# tkl3.net
KiCad netlist of a schematic drawn in EAGLE
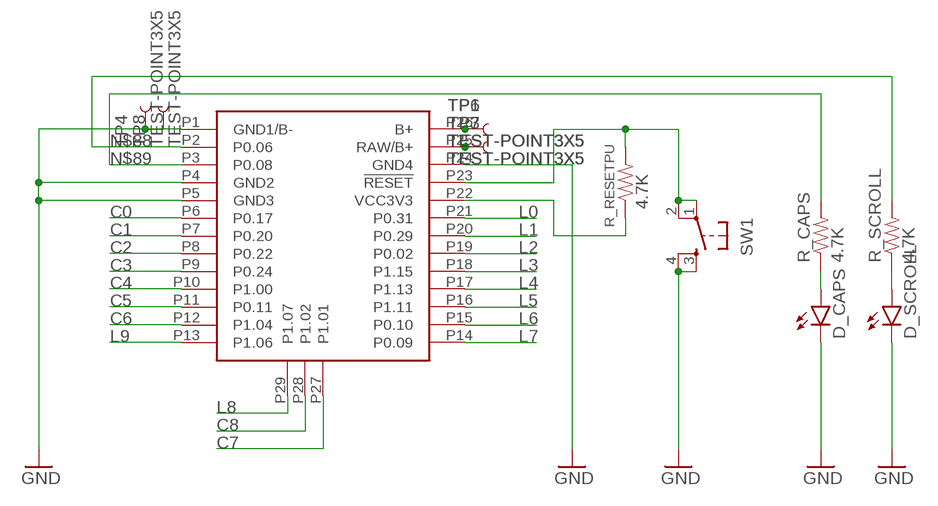
[diagram p0: schematic, sheet 1, part 1 of 2]
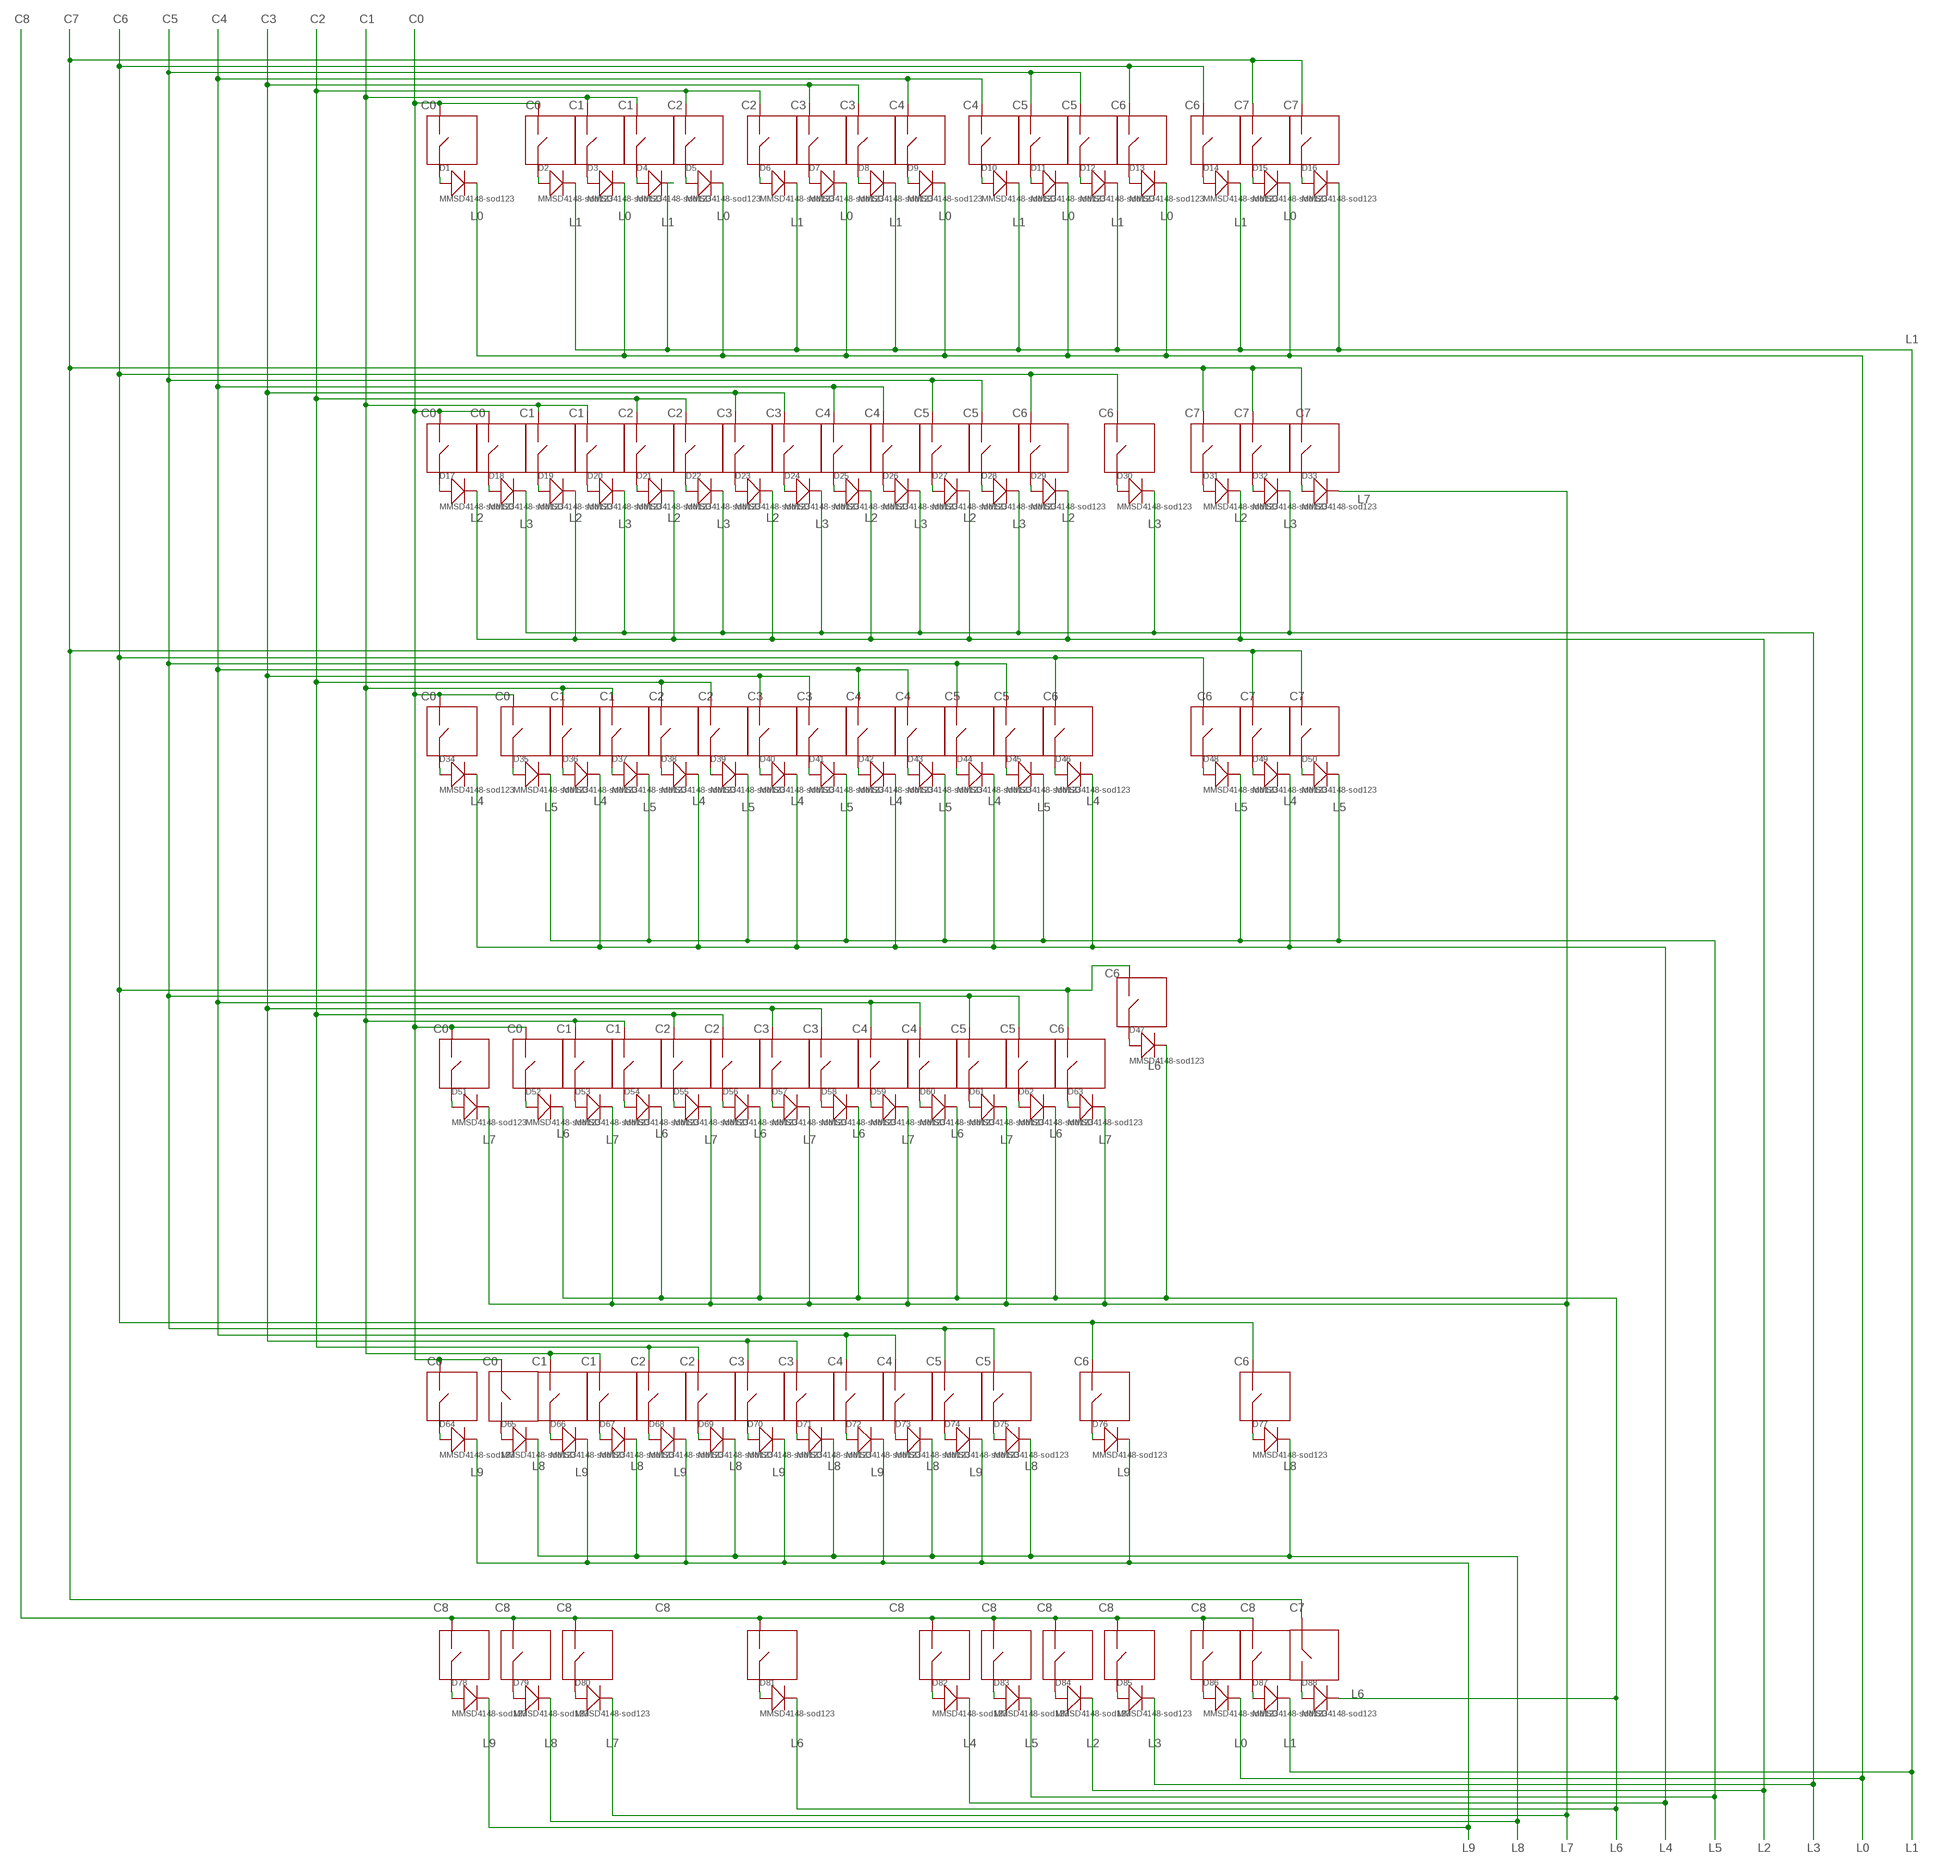
[diagram p1: schematic, sheet 1, part 2 of 2]

(export (version "E")
  (design (tool "Eeschema 10.0.6"))
  (components
    (comp (ref "D1")
      (value "MMSD4148-sod123")
      (footprint "eagle-import:SOD-123")
      (fields (field (name "MPN") "MMSD4148"))
      (libsource (lib "eagle-import") (part "SMD-DIODE-100V-200MA(SOD-123)"))
    )
    (comp (ref "D2")
      (value "MMSD4148-sod123")
      (footprint "eagle-import:SOD-123")
      (fields (field (name "MPN") "MMSD4148"))
      (libsource (lib "eagle-import") (part "SMD-DIODE-100V-200MA(SOD-123)"))
    )
    (comp (ref "D3")
      (value "MMSD4148-sod123")
      (footprint "eagle-import:SOD-123")
      (fields (field (name "MPN") "MMSD4148"))
      (libsource (lib "eagle-import") (part "SMD-DIODE-100V-200MA(SOD-123)"))
    )
    (comp (ref "D4")
      (value "MMSD4148-sod123")
      (footprint "eagle-import:SOD-123")
      (fields (field (name "MPN") "MMSD4148"))
      (libsource (lib "eagle-import") (part "SMD-DIODE-100V-200MA(SOD-123)"))
    )
    (comp (ref "D5")
      (value "MMSD4148-sod123")
      (footprint "eagle-import:SOD-123")
      (fields (field (name "MPN") "MMSD4148"))
      (libsource (lib "eagle-import") (part "SMD-DIODE-100V-200MA(SOD-123)"))
    )
    (comp (ref "D6")
      (value "MMSD4148-sod123")
      (footprint "eagle-import:SOD-123")
      (fields (field (name "MPN") "MMSD4148"))
      (libsource (lib "eagle-import") (part "SMD-DIODE-100V-200MA(SOD-123)"))
    )
    (comp (ref "D7")
      (value "MMSD4148-sod123")
      (footprint "eagle-import:SOD-123")
      (fields (field (name "MPN") "MMSD4148"))
      (libsource (lib "eagle-import") (part "SMD-DIODE-100V-200MA(SOD-123)"))
    )
    (comp (ref "D8")
      (value "MMSD4148-sod123")
      (footprint "eagle-import:SOD-123")
      (fields (field (name "MPN") "MMSD4148"))
      (libsource (lib "eagle-import") (part "SMD-DIODE-100V-200MA(SOD-123)"))
    )
    (comp (ref "D9")
      (value "MMSD4148-sod123")
      (footprint "eagle-import:SOD-123")
      (fields (field (name "MPN") "MMSD4148"))
      (libsource (lib "eagle-import") (part "SMD-DIODE-100V-200MA(SOD-123)"))
    )
    (comp (ref "D10")
      (value "MMSD4148-sod123")
      (footprint "eagle-import:SOD-123")
      (fields (field (name "MPN") "MMSD4148"))
      (libsource (lib "eagle-import") (part "SMD-DIODE-100V-200MA(SOD-123)"))
    )
    (comp (ref "D11")
      (value "MMSD4148-sod123")
      (footprint "eagle-import:SOD-123")
      (fields (field (name "MPN") "MMSD4148"))
      (libsource (lib "eagle-import") (part "SMD-DIODE-100V-200MA(SOD-123)"))
    )
    (comp (ref "D12")
      (value "MMSD4148-sod123")
      (footprint "eagle-import:SOD-123")
      (fields (field (name "MPN") "MMSD4148"))
      (libsource (lib "eagle-import") (part "SMD-DIODE-100V-200MA(SOD-123)"))
    )
    (comp (ref "D13")
      (value "MMSD4148-sod123")
      (footprint "eagle-import:SOD-123")
      (fields (field (name "MPN") "MMSD4148"))
      (libsource (lib "eagle-import") (part "SMD-DIODE-100V-200MA(SOD-123)"))
    )
    (comp (ref "D14")
      (value "MMSD4148-sod123")
      (footprint "eagle-import:SOD-123")
      (fields (field (name "MPN") "MMSD4148"))
      (libsource (lib "eagle-import") (part "SMD-DIODE-100V-200MA(SOD-123)"))
    )
    (comp (ref "D15")
      (value "MMSD4148-sod123")
      (footprint "eagle-import:SOD-123")
      (fields (field (name "MPN") "MMSD4148"))
      (libsource (lib "eagle-import") (part "SMD-DIODE-100V-200MA(SOD-123)"))
    )
    (comp (ref "D16")
      (value "MMSD4148-sod123")
      (footprint "eagle-import:SOD-123")
      (fields (field (name "MPN") "MMSD4148"))
      (libsource (lib "eagle-import") (part "SMD-DIODE-100V-200MA(SOD-123)"))
    )
    (comp (ref "D17")
      (value "MMSD4148-sod123")
      (footprint "eagle-import:SOD-123")
      (fields (field (name "MPN") "MMSD4148"))
      (libsource (lib "eagle-import") (part "SMD-DIODE-100V-200MA(SOD-123)"))
    )
    (comp (ref "D18")
      (value "MMSD4148-sod123")
      (footprint "eagle-import:SOD-123")
      (fields (field (name "MPN") "MMSD4148"))
      (libsource (lib "eagle-import") (part "SMD-DIODE-100V-200MA(SOD-123)"))
    )
    (comp (ref "D19")
      (value "MMSD4148-sod123")
      (footprint "eagle-import:SOD-123")
      (fields (field (name "MPN") "MMSD4148"))
      (libsource (lib "eagle-import") (part "SMD-DIODE-100V-200MA(SOD-123)"))
    )
    (comp (ref "D20")
      (value "MMSD4148-sod123")
      (footprint "eagle-import:SOD-123")
      (fields (field (name "MPN") "MMSD4148"))
      (libsource (lib "eagle-import") (part "SMD-DIODE-100V-200MA(SOD-123)"))
    )
    (comp (ref "D21")
      (value "MMSD4148-sod123")
      (footprint "eagle-import:SOD-123")
      (fields (field (name "MPN") "MMSD4148"))
      (libsource (lib "eagle-import") (part "SMD-DIODE-100V-200MA(SOD-123)"))
    )
    (comp (ref "D22")
      (value "MMSD4148-sod123")
      (footprint "eagle-import:SOD-123")
      (fields (field (name "MPN") "MMSD4148"))
      (libsource (lib "eagle-import") (part "SMD-DIODE-100V-200MA(SOD-123)"))
    )
    (comp (ref "D23")
      (value "MMSD4148-sod123")
      (footprint "eagle-import:SOD-123")
      (fields (field (name "MPN") "MMSD4148"))
      (libsource (lib "eagle-import") (part "SMD-DIODE-100V-200MA(SOD-123)"))
    )
    (comp (ref "D24")
      (value "MMSD4148-sod123")
      (footprint "eagle-import:SOD-123")
      (fields (field (name "MPN") "MMSD4148"))
      (libsource (lib "eagle-import") (part "SMD-DIODE-100V-200MA(SOD-123)"))
    )
    (comp (ref "D25")
      (value "MMSD4148-sod123")
      (footprint "eagle-import:SOD-123")
      (fields (field (name "MPN") "MMSD4148"))
      (libsource (lib "eagle-import") (part "SMD-DIODE-100V-200MA(SOD-123)"))
    )
    (comp (ref "D26")
      (value "MMSD4148-sod123")
      (footprint "eagle-import:SOD-123")
      (fields (field (name "MPN") "MMSD4148"))
      (libsource (lib "eagle-import") (part "SMD-DIODE-100V-200MA(SOD-123)"))
    )
    (comp (ref "D27")
      (value "MMSD4148-sod123")
      (footprint "eagle-import:SOD-123")
      (fields (field (name "MPN") "MMSD4148"))
      (libsource (lib "eagle-import") (part "SMD-DIODE-100V-200MA(SOD-123)"))
    )
    (comp (ref "D28")
      (value "MMSD4148-sod123")
      (footprint "eagle-import:SOD-123")
      (fields (field (name "MPN") "MMSD4148"))
      (libsource (lib "eagle-import") (part "SMD-DIODE-100V-200MA(SOD-123)"))
    )
    (comp (ref "D29")
      (value "MMSD4148-sod123")
      (footprint "eagle-import:SOD-123")
      (fields (field (name "MPN") "MMSD4148"))
      (libsource (lib "eagle-import") (part "SMD-DIODE-100V-200MA(SOD-123)"))
    )
    (comp (ref "D30")
      (value "MMSD4148-sod123")
      (footprint "eagle-import:SOD-123")
      (fields (field (name "MPN") "MMSD4148"))
      (libsource (lib "eagle-import") (part "SMD-DIODE-100V-200MA(SOD-123)"))
    )
    (comp (ref "D31")
      (value "MMSD4148-sod123")
      (footprint "eagle-import:SOD-123")
      (fields (field (name "MPN") "MMSD4148"))
      (libsource (lib "eagle-import") (part "SMD-DIODE-100V-200MA(SOD-123)"))
    )
    (comp (ref "D32")
      (value "MMSD4148-sod123")
      (footprint "eagle-import:SOD-123")
      (fields (field (name "MPN") "MMSD4148"))
      (libsource (lib "eagle-import") (part "SMD-DIODE-100V-200MA(SOD-123)"))
    )
    (comp (ref "D33")
      (value "MMSD4148-sod123")
      (footprint "eagle-import:SOD-123")
      (fields (field (name "MPN") "MMSD4148"))
      (libsource (lib "eagle-import") (part "SMD-DIODE-100V-200MA(SOD-123)"))
    )
    (comp (ref "D34")
      (value "MMSD4148-sod123")
      (footprint "eagle-import:SOD-123")
      (fields (field (name "MPN") "MMSD4148"))
      (libsource (lib "eagle-import") (part "SMD-DIODE-100V-200MA(SOD-123)"))
    )
    (comp (ref "D35")
      (value "MMSD4148-sod123")
      (footprint "eagle-import:SOD-123")
      (fields (field (name "MPN") "MMSD4148"))
      (libsource (lib "eagle-import") (part "SMD-DIODE-100V-200MA(SOD-123)"))
    )
    (comp (ref "D36")
      (value "MMSD4148-sod123")
      (footprint "eagle-import:SOD-123")
      (fields (field (name "MPN") "MMSD4148"))
      (libsource (lib "eagle-import") (part "SMD-DIODE-100V-200MA(SOD-123)"))
    )
    (comp (ref "D37")
      (value "MMSD4148-sod123")
      (footprint "eagle-import:SOD-123")
      (fields (field (name "MPN") "MMSD4148"))
      (libsource (lib "eagle-import") (part "SMD-DIODE-100V-200MA(SOD-123)"))
    )
    (comp (ref "D38")
      (value "MMSD4148-sod123")
      (footprint "eagle-import:SOD-123")
      (fields (field (name "MPN") "MMSD4148"))
      (libsource (lib "eagle-import") (part "SMD-DIODE-100V-200MA(SOD-123)"))
    )
    (comp (ref "D39")
      (value "MMSD4148-sod123")
      (footprint "eagle-import:SOD-123")
      (fields (field (name "MPN") "MMSD4148"))
      (libsource (lib "eagle-import") (part "SMD-DIODE-100V-200MA(SOD-123)"))
    )
    (comp (ref "D40")
      (value "MMSD4148-sod123")
      (footprint "eagle-import:SOD-123")
      (fields (field (name "MPN") "MMSD4148"))
      (libsource (lib "eagle-import") (part "SMD-DIODE-100V-200MA(SOD-123)"))
    )
    (comp (ref "D41")
      (value "MMSD4148-sod123")
      (footprint "eagle-import:SOD-123")
      (fields (field (name "MPN") "MMSD4148"))
      (libsource (lib "eagle-import") (part "SMD-DIODE-100V-200MA(SOD-123)"))
    )
    (comp (ref "D42")
      (value "MMSD4148-sod123")
      (footprint "eagle-import:SOD-123")
      (fields (field (name "MPN") "MMSD4148"))
      (libsource (lib "eagle-import") (part "SMD-DIODE-100V-200MA(SOD-123)"))
    )
    (comp (ref "D43")
      (value "MMSD4148-sod123")
      (footprint "eagle-import:SOD-123")
      (fields (field (name "MPN") "MMSD4148"))
      (libsource (lib "eagle-import") (part "SMD-DIODE-100V-200MA(SOD-123)"))
    )
    (comp (ref "D44")
      (value "MMSD4148-sod123")
      (footprint "eagle-import:SOD-123")
      (fields (field (name "MPN") "MMSD4148"))
      (libsource (lib "eagle-import") (part "SMD-DIODE-100V-200MA(SOD-123)"))
    )
    (comp (ref "D45")
      (value "MMSD4148-sod123")
      (footprint "eagle-import:SOD-123")
      (fields (field (name "MPN") "MMSD4148"))
      (libsource (lib "eagle-import") (part "SMD-DIODE-100V-200MA(SOD-123)"))
    )
    (comp (ref "D46")
      (value "MMSD4148-sod123")
      (footprint "eagle-import:SOD-123")
      (fields (field (name "MPN") "MMSD4148"))
      (libsource (lib "eagle-import") (part "SMD-DIODE-100V-200MA(SOD-123)"))
    )
    (comp (ref "D47")
      (value "MMSD4148-sod123")
      (footprint "eagle-import:SOD-123")
      (fields (field (name "MPN") "MMSD4148"))
      (libsource (lib "eagle-import") (part "SMD-DIODE-100V-200MA(SOD-123)"))
    )
    (comp (ref "D48")
      (value "MMSD4148-sod123")
      (footprint "eagle-import:SOD-123")
      (fields (field (name "MPN") "MMSD4148"))
      (libsource (lib "eagle-import") (part "SMD-DIODE-100V-200MA(SOD-123)"))
    )
    (comp (ref "D49")
      (value "MMSD4148-sod123")
      (footprint "eagle-import:SOD-123")
      (fields (field (name "MPN") "MMSD4148"))
      (libsource (lib "eagle-import") (part "SMD-DIODE-100V-200MA(SOD-123)"))
    )
    (comp (ref "D50")
      (value "MMSD4148-sod123")
      (footprint "eagle-import:SOD-123")
      (fields (field (name "MPN") "MMSD4148"))
      (libsource (lib "eagle-import") (part "SMD-DIODE-100V-200MA(SOD-123)"))
    )
    (comp (ref "D51")
      (value "MMSD4148-sod123")
      (footprint "eagle-import:SOD-123")
      (fields (field (name "MPN") "MMSD4148"))
      (libsource (lib "eagle-import") (part "SMD-DIODE-100V-200MA(SOD-123)"))
    )
    (comp (ref "D52")
      (value "MMSD4148-sod123")
      (footprint "eagle-import:SOD-123")
      (fields (field (name "MPN") "MMSD4148"))
      (libsource (lib "eagle-import") (part "SMD-DIODE-100V-200MA(SOD-123)"))
    )
    (comp (ref "D53")
      (value "MMSD4148-sod123")
      (footprint "eagle-import:SOD-123")
      (fields (field (name "MPN") "MMSD4148"))
      (libsource (lib "eagle-import") (part "SMD-DIODE-100V-200MA(SOD-123)"))
    )
    (comp (ref "D54")
      (value "MMSD4148-sod123")
      (footprint "eagle-import:SOD-123")
      (fields (field (name "MPN") "MMSD4148"))
      (libsource (lib "eagle-import") (part "SMD-DIODE-100V-200MA(SOD-123)"))
    )
    (comp (ref "D55")
      (value "MMSD4148-sod123")
      (footprint "eagle-import:SOD-123")
      (fields (field (name "MPN") "MMSD4148"))
      (libsource (lib "eagle-import") (part "SMD-DIODE-100V-200MA(SOD-123)"))
    )
    (comp (ref "D56")
      (value "MMSD4148-sod123")
      (footprint "eagle-import:SOD-123")
      (fields (field (name "MPN") "MMSD4148"))
      (libsource (lib "eagle-import") (part "SMD-DIODE-100V-200MA(SOD-123)"))
    )
    (comp (ref "D57")
      (value "MMSD4148-sod123")
      (footprint "eagle-import:SOD-123")
      (fields (field (name "MPN") "MMSD4148"))
      (libsource (lib "eagle-import") (part "SMD-DIODE-100V-200MA(SOD-123)"))
    )
    (comp (ref "D58")
      (value "MMSD4148-sod123")
      (footprint "eagle-import:SOD-123")
      (fields (field (name "MPN") "MMSD4148"))
      (libsource (lib "eagle-import") (part "SMD-DIODE-100V-200MA(SOD-123)"))
    )
    (comp (ref "D59")
      (value "MMSD4148-sod123")
      (footprint "eagle-import:SOD-123")
      (fields (field (name "MPN") "MMSD4148"))
      (libsource (lib "eagle-import") (part "SMD-DIODE-100V-200MA(SOD-123)"))
    )
    (comp (ref "D60")
      (value "MMSD4148-sod123")
      (footprint "eagle-import:SOD-123")
      (fields (field (name "MPN") "MMSD4148"))
      (libsource (lib "eagle-import") (part "SMD-DIODE-100V-200MA(SOD-123)"))
    )
    (comp (ref "D61")
      (value "MMSD4148-sod123")
      (footprint "eagle-import:SOD-123")
      (fields (field (name "MPN") "MMSD4148"))
      (libsource (lib "eagle-import") (part "SMD-DIODE-100V-200MA(SOD-123)"))
    )
    (comp (ref "D62")
      (value "MMSD4148-sod123")
      (footprint "eagle-import:SOD-123")
      (fields (field (name "MPN") "MMSD4148"))
      (libsource (lib "eagle-import") (part "SMD-DIODE-100V-200MA(SOD-123)"))
    )
    (comp (ref "D63")
      (value "MMSD4148-sod123")
      (footprint "eagle-import:SOD-123")
      (fields (field (name "MPN") "MMSD4148"))
      (libsource (lib "eagle-import") (part "SMD-DIODE-100V-200MA(SOD-123)"))
    )
    (comp (ref "D64")
      (value "MMSD4148-sod123")
      (footprint "eagle-import:SOD-123")
      (fields (field (name "MPN") "MMSD4148"))
      (libsource (lib "eagle-import") (part "SMD-DIODE-100V-200MA(SOD-123)"))
    )
    (comp (ref "D65")
      (value "MMSD4148-sod123")
      (footprint "eagle-import:SOD-123")
      (fields (field (name "MPN") "MMSD4148"))
      (libsource (lib "eagle-import") (part "SMD-DIODE-100V-200MA(SOD-123)"))
    )
    (comp (ref "D66")
      (value "MMSD4148-sod123")
      (footprint "eagle-import:SOD-123")
      (fields (field (name "MPN") "MMSD4148"))
      (libsource (lib "eagle-import") (part "SMD-DIODE-100V-200MA(SOD-123)"))
    )
    (comp (ref "D67")
      (value "MMSD4148-sod123")
      (footprint "eagle-import:SOD-123")
      (fields (field (name "MPN") "MMSD4148"))
      (libsource (lib "eagle-import") (part "SMD-DIODE-100V-200MA(SOD-123)"))
    )
    (comp (ref "D68")
      (value "MMSD4148-sod123")
      (footprint "eagle-import:SOD-123")
      (fields (field (name "MPN") "MMSD4148"))
      (libsource (lib "eagle-import") (part "SMD-DIODE-100V-200MA(SOD-123)"))
    )
    (comp (ref "D69")
      (value "MMSD4148-sod123")
      (footprint "eagle-import:SOD-123")
      (fields (field (name "MPN") "MMSD4148"))
      (libsource (lib "eagle-import") (part "SMD-DIODE-100V-200MA(SOD-123)"))
    )
    (comp (ref "D70")
      (value "MMSD4148-sod123")
      (footprint "eagle-import:SOD-123")
      (fields (field (name "MPN") "MMSD4148"))
      (libsource (lib "eagle-import") (part "SMD-DIODE-100V-200MA(SOD-123)"))
    )
    (comp (ref "D71")
      (value "MMSD4148-sod123")
      (footprint "eagle-import:SOD-123")
      (fields (field (name "MPN") "MMSD4148"))
      (libsource (lib "eagle-import") (part "SMD-DIODE-100V-200MA(SOD-123)"))
    )
    (comp (ref "D72")
      (value "MMSD4148-sod123")
      (footprint "eagle-import:SOD-123")
      (fields (field (name "MPN") "MMSD4148"))
      (libsource (lib "eagle-import") (part "SMD-DIODE-100V-200MA(SOD-123)"))
    )
    (comp (ref "D73")
      (value "MMSD4148-sod123")
      (footprint "eagle-import:SOD-123")
      (fields (field (name "MPN") "MMSD4148"))
      (libsource (lib "eagle-import") (part "SMD-DIODE-100V-200MA(SOD-123)"))
    )
    (comp (ref "D74")
      (value "MMSD4148-sod123")
      (footprint "eagle-import:SOD-123")
      (fields (field (name "MPN") "MMSD4148"))
      (libsource (lib "eagle-import") (part "SMD-DIODE-100V-200MA(SOD-123)"))
    )
    (comp (ref "D75")
      (value "MMSD4148-sod123")
      (footprint "eagle-import:SOD-123")
      (fields (field (name "MPN") "MMSD4148"))
      (libsource (lib "eagle-import") (part "SMD-DIODE-100V-200MA(SOD-123)"))
    )
    (comp (ref "D76")
      (value "MMSD4148-sod123")
      (footprint "eagle-import:SOD-123")
      (fields (field (name "MPN") "MMSD4148"))
      (libsource (lib "eagle-import") (part "SMD-DIODE-100V-200MA(SOD-123)"))
    )
    (comp (ref "D77")
      (value "MMSD4148-sod123")
      (footprint "eagle-import:SOD-123")
      (fields (field (name "MPN") "MMSD4148"))
      (libsource (lib "eagle-import") (part "SMD-DIODE-100V-200MA(SOD-123)"))
    )
    (comp (ref "D78")
      (value "MMSD4148-sod123")
      (footprint "eagle-import:SOD-123")
      (fields (field (name "MPN") "MMSD4148"))
      (libsource (lib "eagle-import") (part "SMD-DIODE-100V-200MA(SOD-123)"))
    )
    (comp (ref "D79")
      (value "MMSD4148-sod123")
      (footprint "eagle-import:SOD-123")
      (fields (field (name "MPN") "MMSD4148"))
      (libsource (lib "eagle-import") (part "SMD-DIODE-100V-200MA(SOD-123)"))
    )
    (comp (ref "D80")
      (value "MMSD4148-sod123")
      (footprint "eagle-import:SOD-123")
      (fields (field (name "MPN") "MMSD4148"))
      (libsource (lib "eagle-import") (part "SMD-DIODE-100V-200MA(SOD-123)"))
    )
    (comp (ref "D81")
      (value "MMSD4148-sod123")
      (footprint "eagle-import:SOD-123")
      (fields (field (name "MPN") "MMSD4148"))
      (libsource (lib "eagle-import") (part "SMD-DIODE-100V-200MA(SOD-123)"))
    )
    (comp (ref "D82")
      (value "MMSD4148-sod123")
      (footprint "eagle-import:SOD-123")
      (fields (field (name "MPN") "MMSD4148"))
      (libsource (lib "eagle-import") (part "SMD-DIODE-100V-200MA(SOD-123)"))
    )
    (comp (ref "D83")
      (value "MMSD4148-sod123")
      (footprint "eagle-import:SOD-123")
      (fields (field (name "MPN") "MMSD4148"))
      (libsource (lib "eagle-import") (part "SMD-DIODE-100V-200MA(SOD-123)"))
    )
    (comp (ref "D84")
      (value "MMSD4148-sod123")
      (footprint "eagle-import:SOD-123")
      (fields (field (name "MPN") "MMSD4148"))
      (libsource (lib "eagle-import") (part "SMD-DIODE-100V-200MA(SOD-123)"))
    )
    (comp (ref "D85")
      (value "MMSD4148-sod123")
      (footprint "eagle-import:SOD-123")
      (fields (field (name "MPN") "MMSD4148"))
      (libsource (lib "eagle-import") (part "SMD-DIODE-100V-200MA(SOD-123)"))
    )
    (comp (ref "D86")
      (value "MMSD4148-sod123")
      (footprint "eagle-import:SOD-123")
      (fields (field (name "MPN") "MMSD4148"))
      (libsource (lib "eagle-import") (part "SMD-DIODE-100V-200MA(SOD-123)"))
    )
    (comp (ref "D87")
      (value "MMSD4148-sod123")
      (footprint "eagle-import:SOD-123")
      (fields (field (name "MPN") "MMSD4148"))
      (libsource (lib "eagle-import") (part "SMD-DIODE-100V-200MA(SOD-123)"))
    )
    (comp (ref "D88")
      (value "MMSD4148-sod123")
      (footprint "eagle-import:SOD-123")
      (fields (field (name "MPN") "MMSD4148"))
      (libsource (lib "eagle-import") (part "SMD-DIODE-100V-200MA(SOD-123)"))
    )
    (comp (ref "D_CAPS")
      (value "LED3MM")
      (footprint "eagle-import:LED3MM")
      (libsource (lib "eagle-import") (part "LED3MM"))
    )
    (comp (ref "D_SCROLL")
      (value "LED3MM")
      (footprint "eagle-import:LED3MM")
      (libsource (lib "eagle-import") (part "LED3MM"))
    )
    (comp (ref "F_F2")
      (value "CHERRY_MX1U")
      (footprint "eagle-import:CHERRY_MX_NO_LED_SOCKET_1U")
      (libsource (lib "eagle-import") (part "CHERRY_MX1U"))
    )
    (comp (ref "K_0")
      (value "CHERRY_MX1U")
      (footprint "eagle-import:CHERRY_MX_NO_LED_SOCKET_1U")
      (libsource (lib "eagle-import") (part "CHERRY_MX1U"))
    )
    (comp (ref "K_1")
      (value "CHERRY_MX1U")
      (footprint "eagle-import:CHERRY_MX_NO_LED_SOCKET_1U")
      (libsource (lib "eagle-import") (part "CHERRY_MX1U"))
    )
    (comp (ref "K_2")
      (value "CHERRY_MX1U")
      (footprint "eagle-import:CHERRY_MX_NO_LED_SOCKET_1U")
      (libsource (lib "eagle-import") (part "CHERRY_MX1U"))
    )
    (comp (ref "K_3")
      (value "CHERRY_MX1U")
      (footprint "eagle-import:CHERRY_MX_NO_LED_SOCKET_1U")
      (libsource (lib "eagle-import") (part "CHERRY_MX1U"))
    )
    (comp (ref "K_4")
      (value "CHERRY_MX1U")
      (footprint "eagle-import:CHERRY_MX_NO_LED_SOCKET_1U")
      (libsource (lib "eagle-import") (part "CHERRY_MX1U"))
    )
    (comp (ref "K_5")
      (value "CHERRY_MX1U")
      (footprint "eagle-import:CHERRY_MX_NO_LED_SOCKET_1U")
      (libsource (lib "eagle-import") (part "CHERRY_MX1U"))
    )
    (comp (ref "K_6")
      (value "CHERRY_MX1U")
      (footprint "eagle-import:CHERRY_MX_NO_LED_SOCKET_1U")
      (libsource (lib "eagle-import") (part "CHERRY_MX1U"))
    )
    (comp (ref "K_7")
      (value "CHERRY_MX1U")
      (footprint "eagle-import:CHERRY_MX_NO_LED_SOCKET_1U")
      (libsource (lib "eagle-import") (part "CHERRY_MX1U"))
    )
    (comp (ref "K_8")
      (value "CHERRY_MX1U")
      (footprint "eagle-import:CHERRY_MX_NO_LED_SOCKET_1U")
      (libsource (lib "eagle-import") (part "CHERRY_MX1U"))
    )
    (comp (ref "K_9")
      (value "CHERRY_MX1U")
      (footprint "eagle-import:CHERRY_MX_NO_LED_SOCKET_1U")
      (libsource (lib "eagle-import") (part "CHERRY_MX1U"))
    )
    (comp (ref "K_A")
      (value "CHERRY_MX1U")
      (footprint "eagle-import:CHERRY_MX_NO_LED_SOCKET_1U")
      (libsource (lib "eagle-import") (part "CHERRY_MX1U"))
    )
    (comp (ref "K_B")
      (value "CHERRY_MX1U")
      (footprint "eagle-import:CHERRY_MX_NO_LED_SOCKET_1U")
      (libsource (lib "eagle-import") (part "CHERRY_MX1U"))
    )
    (comp (ref "K_BACK")
      (value "CHERRY_MX1U")
      (footprint "eagle-import:CHERRY_MX_NO_LED_SOCKET_1U")
      (libsource (lib "eagle-import") (part "CHERRY_MX1U"))
    )
    (comp (ref "K_C")
      (value "CHERRY_MX1U")
      (footprint "eagle-import:CHERRY_MX_NO_LED_SOCKET_1U")
      (libsource (lib "eagle-import") (part "CHERRY_MX1U"))
    )
    (comp (ref "K_CAPSLOCK")
      (value "CHERRY_MX1U")
      (footprint "eagle-import:CHERRY_MX_NO_LED_SOCKET_1U")
      (libsource (lib "eagle-import") (part "CHERRY_MX1U"))
    )
    (comp (ref "K_COMA")
      (value "CHERRY_MX1U")
      (footprint "eagle-import:CHERRY_MX_NO_LED_SOCKET_1U")
      (libsource (lib "eagle-import") (part "CHERRY_MX1U"))
    )
    (comp (ref "K_D")
      (value "CHERRY_MX1U")
      (footprint "eagle-import:CHERRY_MX_NO_LED_SOCKET_1U")
      (libsource (lib "eagle-import") (part "CHERRY_MX1U"))
    )
    (comp (ref "K_DELETE")
      (value "CHERRY_MX1U")
      (footprint "eagle-import:CHERRY_MX_NO_LED_SOCKET_1U")
      (libsource (lib "eagle-import") (part "CHERRY_MX1U"))
    )
    (comp (ref "K_DOT")
      (value "CHERRY_MX1U")
      (footprint "eagle-import:CHERRY_MX_NO_LED_SOCKET_1U")
      (libsource (lib "eagle-import") (part "CHERRY_MX1U"))
    )
    (comp (ref "K_DOWN")
      (value "CHERRY_MX1U")
      (footprint "eagle-import:CHERRY_MX_NO_LED_SOCKET_1U")
      (libsource (lib "eagle-import") (part "CHERRY_MX1U"))
    )
    (comp (ref "K_E")
      (value "CHERRY_MX1U")
      (footprint "eagle-import:CHERRY_MX_NO_LED_SOCKET_1U")
      (libsource (lib "eagle-import") (part "CHERRY_MX1U"))
    )
    (comp (ref "K_ECH")
      (value "CHERRY_MX1U")
      (footprint "eagle-import:CHERRY_MX_NO_LED_SOCKET_1U")
      (libsource (lib "eagle-import") (part "CHERRY_MX1U"))
    )
    (comp (ref "K_END")
      (value "CHERRY_MX1U")
      (footprint "eagle-import:CHERRY_MX_NO_LED_SOCKET_1U")
      (libsource (lib "eagle-import") (part "CHERRY_MX1U"))
    )
    (comp (ref "K_ENTER")
      (value "CHERRY_MX1U")
      (footprint "eagle-import:CHERRY_MX_NO_LED_SOCKET_1U")
      (libsource (lib "eagle-import") (part "CHERRY_MX1U"))
    )
    (comp (ref "K_F")
      (value "CHERRY_MX1U")
      (footprint "eagle-import:CHERRY_MX_NO_LED_SOCKET_1U")
      (libsource (lib "eagle-import") (part "CHERRY_MX1U"))
    )
    (comp (ref "K_F1")
      (value "CHERRY_MX1U")
      (footprint "eagle-import:CHERRY_MX_NO_LED_SOCKET_1U")
      (libsource (lib "eagle-import") (part "CHERRY_MX1U"))
    )
    (comp (ref "K_F3")
      (value "CHERRY_MX1U")
      (footprint "eagle-import:CHERRY_MX_NO_LED_SOCKET_1U")
      (libsource (lib "eagle-import") (part "CHERRY_MX1U"))
    )
    (comp (ref "K_F4")
      (value "CHERRY_MX1U")
      (footprint "eagle-import:CHERRY_MX_NO_LED_SOCKET_1U")
      (libsource (lib "eagle-import") (part "CHERRY_MX1U"))
    )
    (comp (ref "K_F5")
      (value "CHERRY_MX1U")
      (footprint "eagle-import:CHERRY_MX_NO_LED_SOCKET_1U")
      (libsource (lib "eagle-import") (part "CHERRY_MX1U"))
    )
    (comp (ref "K_F6")
      (value "CHERRY_MX1U")
      (footprint "eagle-import:CHERRY_MX_NO_LED_SOCKET_1U")
      (libsource (lib "eagle-import") (part "CHERRY_MX1U"))
    )
    (comp (ref "K_F7")
      (value "CHERRY_MX1U")
      (footprint "eagle-import:CHERRY_MX_NO_LED_SOCKET_1U")
      (libsource (lib "eagle-import") (part "CHERRY_MX1U"))
    )
    (comp (ref "K_F8")
      (value "CHERRY_MX1U")
      (footprint "eagle-import:CHERRY_MX_NO_LED_SOCKET_1U")
      (libsource (lib "eagle-import") (part "CHERRY_MX1U"))
    )
    (comp (ref "K_F9")
      (value "CHERRY_MX1U")
      (footprint "eagle-import:CHERRY_MX_NO_LED_SOCKET_1U")
      (libsource (lib "eagle-import") (part "CHERRY_MX1U"))
    )
    (comp (ref "K_F10")
      (value "CHERRY_MX1U")
      (footprint "eagle-import:CHERRY_MX_NO_LED_SOCKET_1U")
      (libsource (lib "eagle-import") (part "CHERRY_MX1U"))
    )
    (comp (ref "K_F11")
      (value "CHERRY_MX1U")
      (footprint "eagle-import:CHERRY_MX_NO_LED_SOCKET_1U")
      (libsource (lib "eagle-import") (part "CHERRY_MX1U"))
    )
    (comp (ref "K_F12")
      (value "CHERRY_MX1U")
      (footprint "eagle-import:CHERRY_MX_NO_LED_SOCKET_1U")
      (libsource (lib "eagle-import") (part "CHERRY_MX1U"))
    )
    (comp (ref "K_FN")
      (value "CHERRY_MX1U")
      (footprint "eagle-import:CHERRY_MX_NO_LED_SOCKET_1U")
      (libsource (lib "eagle-import") (part "CHERRY_MX1U"))
    )
    (comp (ref "K_G")
      (value "CHERRY_MX1U")
      (footprint "eagle-import:CHERRY_MX_NO_LED_SOCKET_1U")
      (libsource (lib "eagle-import") (part "CHERRY_MX1U"))
    )
    (comp (ref "K_H")
      (value "CHERRY_MX1U")
      (footprint "eagle-import:CHERRY_MX_NO_LED_SOCKET_1U")
      (libsource (lib "eagle-import") (part "CHERRY_MX1U"))
    )
    (comp (ref "K_HOME")
      (value "CHERRY_MX1U")
      (footprint "eagle-import:CHERRY_MX_NO_LED_SOCKET_1U")
      (libsource (lib "eagle-import") (part "CHERRY_MX1U"))
    )
    (comp (ref "K_I")
      (value "CHERRY_MX1U")
      (footprint "eagle-import:CHERRY_MX_NO_LED_SOCKET_1U")
      (libsource (lib "eagle-import") (part "CHERRY_MX1U"))
    )
    (comp (ref "K_INSERT")
      (value "CHERRY_MX1U")
      (footprint "eagle-import:CHERRY_MX_NO_LED_SOCKET_1U")
      (libsource (lib "eagle-import") (part "CHERRY_MX1U"))
    )
    (comp (ref "K_J")
      (value "CHERRY_MX1U")
      (footprint "eagle-import:CHERRY_MX_NO_LED_SOCKET_1U")
      (libsource (lib "eagle-import") (part "CHERRY_MX1U"))
    )
    (comp (ref "K_K")
      (value "CHERRY_MX1U")
      (footprint "eagle-import:CHERRY_MX_NO_LED_SOCKET_1U")
      (libsource (lib "eagle-import") (part "CHERRY_MX1U"))
    )
    (comp (ref "K_L")
      (value "CHERRY_MX1U")
      (footprint "eagle-import:CHERRY_MX_NO_LED_SOCKET_1U")
      (libsource (lib "eagle-import") (part "CHERRY_MX1U"))
    )
    (comp (ref "K_LALT")
      (value "CHERRY_MX1U")
      (footprint "eagle-import:CHERRY_MX_NO_LED_SOCKET_1U")
      (libsource (lib "eagle-import") (part "CHERRY_MX1U"))
    )
    (comp (ref "K_LBRA")
      (value "CHERRY_MX1U")
      (footprint "eagle-import:CHERRY_MX_NO_LED_SOCKET_1U")
      (libsource (lib "eagle-import") (part "CHERRY_MX1U"))
    )
    (comp (ref "K_LCTRL")
      (value "CHERRY_MX1U")
      (footprint "eagle-import:CHERRY_MX_NO_LED_SOCKET_1U")
      (libsource (lib "eagle-import") (part "CHERRY_MX1U"))
    )
    (comp (ref "K_LEFT")
      (value "CHERRY_MX1U")
      (footprint "eagle-import:CHERRY_MX_NO_LED_SOCKET_1U")
      (libsource (lib "eagle-import") (part "CHERRY_MX1U"))
    )
    (comp (ref "K_LSHFT")
      (value "CHERRY_MX1U")
      (footprint "eagle-import:CHERRY_MX_NO_LED_SOCKET_1U")
      (libsource (lib "eagle-import") (part "CHERRY_MX1U"))
    )
    (comp (ref "K_LWIN")
      (value "CHERRY_MX1U")
      (footprint "eagle-import:CHERRY_MX_NO_LED_SOCKET_1U")
      (libsource (lib "eagle-import") (part "CHERRY_MX1U"))
    )
    (comp (ref "K_M")
      (value "CHERRY_MX1U")
      (footprint "eagle-import:CHERRY_MX_NO_LED_SOCKET_1U")
      (libsource (lib "eagle-import") (part "CHERRY_MX1U"))
    )
    (comp (ref "K_MINUS")
      (value "CHERRY_MX1U")
      (footprint "eagle-import:CHERRY_MX_NO_LED_SOCKET_1U")
      (libsource (lib "eagle-import") (part "CHERRY_MX1U"))
    )
    (comp (ref "K_N")
      (value "CHERRY_MX1U")
      (footprint "eagle-import:CHERRY_MX_NO_LED_SOCKET_1U")
      (libsource (lib "eagle-import") (part "CHERRY_MX1U"))
    )
    (comp (ref "K_O")
      (value "CHERRY_MX1U")
      (footprint "eagle-import:CHERRY_MX_NO_LED_SOCKET_1U")
      (libsource (lib "eagle-import") (part "CHERRY_MX1U"))
    )
    (comp (ref "K_P")
      (value "CHERRY_MX1U")
      (footprint "eagle-import:CHERRY_MX_NO_LED_SOCKET_1U")
      (libsource (lib "eagle-import") (part "CHERRY_MX1U"))
    )
    (comp (ref "K_PAUSE")
      (value "CHERRY_MX1U")
      (footprint "eagle-import:CHERRY_MX_NO_LED_SOCKET_1U")
      (libsource (lib "eagle-import") (part "CHERRY_MX1U"))
    )
    (comp (ref "K_PDW")
      (value "CHERRY_MX1U")
      (footprint "eagle-import:CHERRY_MX_NO_LED_SOCKET_1U")
      (libsource (lib "eagle-import") (part "CHERRY_MX1U"))
    )
    (comp (ref "K_PIPE")
      (value "CHERRY_MX1U")
      (footprint "eagle-import:CHERRY_MX_NO_LED_SOCKET_1U")
      (libsource (lib "eagle-import") (part "CHERRY_MX1U"))
    )
    (comp (ref "K_PLUS")
      (value "CHERRY_MX1U")
      (footprint "eagle-import:CHERRY_MX_NO_LED_SOCKET_1U")
      (libsource (lib "eagle-import") (part "CHERRY_MX1U"))
    )
    (comp (ref "K_PRNT")
      (value "CHERRY_MX1U")
      (footprint "eagle-import:CHERRY_MX_NO_LED_SOCKET_1U")
      (libsource (lib "eagle-import") (part "CHERRY_MX1U"))
    )
    (comp (ref "K_PUP")
      (value "CHERRY_MX1U")
      (footprint "eagle-import:CHERRY_MX_NO_LED_SOCKET_1U")
      (libsource (lib "eagle-import") (part "CHERRY_MX1U"))
    )
    (comp (ref "K_Q")
      (value "CHERRY_MX1U")
      (footprint "eagle-import:CHERRY_MX_NO_LED_SOCKET_1U")
      (libsource (lib "eagle-import") (part "CHERRY_MX1U"))
    )
    (comp (ref "K_QUOTE")
      (value "CHERRY_MX1U")
      (footprint "eagle-import:CHERRY_MX_NO_LED_SOCKET_1U")
      (libsource (lib "eagle-import") (part "CHERRY_MX1U"))
    )
    (comp (ref "K_R")
      (value "CHERRY_MX1U")
      (footprint "eagle-import:CHERRY_MX_NO_LED_SOCKET_1U")
      (libsource (lib "eagle-import") (part "CHERRY_MX1U"))
    )
    (comp (ref "K_RALT")
      (value "CHERRY_MX1U")
      (footprint "eagle-import:CHERRY_MX_NO_LED_SOCKET_1U")
      (libsource (lib "eagle-import") (part "CHERRY_MX1U"))
    )
    (comp (ref "K_RBRA")
      (value "CHERRY_MX1U")
      (footprint "eagle-import:CHERRY_MX_NO_LED_SOCKET_1U")
      (libsource (lib "eagle-import") (part "CHERRY_MX1U"))
    )
    (comp (ref "K_RCTRL")
      (value "CHERRY_MX1U")
      (footprint "eagle-import:CHERRY_MX_NO_LED_SOCKET_1U")
      (libsource (lib "eagle-import") (part "CHERRY_MX1U"))
    )
    (comp (ref "K_RIGHT")
      (value "CHERRY_MX1U")
      (footprint "eagle-import:CHERRY_MX_NO_LED_SOCKET_1U")
      (libsource (lib "eagle-import") (part "CHERRY_MX1U"))
    )
    (comp (ref "K_RSHFT")
      (value "CHERRY_MX1U")
      (footprint "eagle-import:CHERRY_MX_NO_LED_SOCKET_1U")
      (libsource (lib "eagle-import") (part "CHERRY_MX1U"))
    )
    (comp (ref "K_RWIN")
      (value "CHERRY_MX1U")
      (footprint "eagle-import:CHERRY_MX_NO_LED_SOCKET_1U")
      (libsource (lib "eagle-import") (part "CHERRY_MX1U"))
    )
    (comp (ref "K_S")
      (value "CHERRY_MX1U")
      (footprint "eagle-import:CHERRY_MX_NO_LED_SOCKET_1U")
      (libsource (lib "eagle-import") (part "CHERRY_MX1U"))
    )
    (comp (ref "K_SCROL")
      (value "CHERRY_MX1U")
      (footprint "eagle-import:CHERRY_MX_NO_LED_SOCKET_1U")
      (libsource (lib "eagle-import") (part "CHERRY_MX1U"))
    )
    (comp (ref "K_SEMIC")
      (value "CHERRY_MX1U")
      (footprint "eagle-import:CHERRY_MX_NO_LED_SOCKET_1U")
      (libsource (lib "eagle-import") (part "CHERRY_MX1U"))
    )
    (comp (ref "K_SLASH")
      (value "CHERRY_MX1U")
      (footprint "eagle-import:CHERRY_MX_NO_LED_SOCKET_1U")
      (libsource (lib "eagle-import") (part "CHERRY_MX1U"))
    )
    (comp (ref "K_SPACE")
      (value "CHERRY_MX1U")
      (footprint "eagle-import:CHERRY_MX_NO_LED_SOCKET_1U")
      (libsource (lib "eagle-import") (part "CHERRY_MX1U"))
    )
    (comp (ref "K_T")
      (value "CHERRY_MX1U")
      (footprint "eagle-import:CHERRY_MX_NO_LED_SOCKET_1U")
      (libsource (lib "eagle-import") (part "CHERRY_MX1U"))
    )
    (comp (ref "K_TAB")
      (value "CHERRY_MX1U")
      (footprint "eagle-import:CHERRY_MX_NO_LED_SOCKET_1U")
      (libsource (lib "eagle-import") (part "CHERRY_MX1U"))
    )
    (comp (ref "K_U")
      (value "CHERRY_MX1U")
      (footprint "eagle-import:CHERRY_MX_NO_LED_SOCKET_1U")
      (libsource (lib "eagle-import") (part "CHERRY_MX1U"))
    )
    (comp (ref "K_UP")
      (value "CHERRY_MX1U")
      (footprint "eagle-import:CHERRY_MX_NO_LED_SOCKET_1U")
      (libsource (lib "eagle-import") (part "CHERRY_MX1U"))
    )
    (comp (ref "K_V")
      (value "CHERRY_MX1U")
      (footprint "eagle-import:CHERRY_MX_NO_LED_SOCKET_1U")
      (libsource (lib "eagle-import") (part "CHERRY_MX1U"))
    )
    (comp (ref "K_W")
      (value "CHERRY_MX1U")
      (footprint "eagle-import:CHERRY_MX_NO_LED_SOCKET_1U")
      (libsource (lib "eagle-import") (part "CHERRY_MX1U"))
    )
    (comp (ref "K_WAVE")
      (value "CHERRY_MX1U")
      (footprint "eagle-import:CHERRY_MX_NO_LED_SOCKET_1U")
      (libsource (lib "eagle-import") (part "CHERRY_MX1U"))
    )
    (comp (ref "K_X")
      (value "CHERRY_MX1U")
      (footprint "eagle-import:CHERRY_MX_NO_LED_SOCKET_1U")
      (libsource (lib "eagle-import") (part "CHERRY_MX1U"))
    )
    (comp (ref "K_Y")
      (value "CHERRY_MX1U")
      (footprint "eagle-import:CHERRY_MX_NO_LED_SOCKET_1U")
      (libsource (lib "eagle-import") (part "CHERRY_MX1U"))
    )
    (comp (ref "K_Z")
      (value "CHERRY_MX1U")
      (footprint "eagle-import:CHERRY_MX_NO_LED_SOCKET_1U")
      (libsource (lib "eagle-import") (part "CHERRY_MX1U"))
    )
    (comp (ref "R_CAPS")
      (value "4.7K")
      (footprint "eagle-import:0603-RES")
      (libsource (lib "eagle-import") (part "4.7KOHM-1/10W-1%(0603)"))
    )
    (comp (ref "R_RESETPU")
      (value "4.7K")
      (footprint "eagle-import:0603-RES")
      (libsource (lib "eagle-import") (part "4.7KOHM-1/10W-1%(0603)"))
    )
    (comp (ref "R_SCROLL")
      (value "4.7K")
      (footprint "eagle-import:0603-RES")
      (libsource (lib "eagle-import") (part "4.7KOHM-1/10W-1%(0603)"))
    )
    (comp (ref "SW1")
      (value "SWITCH_SPST_4_PINRECT")
      (footprint "eagle-import:TACTILE_SWITCH_SMD_4.6X2.8MM")
      (libsource (lib "eagle-import") (part "SWITCH_SPST_4_PINRECT"))
    )
    (comp (ref "TP1")
      (value "TEST-POINT3X5")
      (footprint "eagle-import:PAD.03X.05")
      (libsource (lib "eagle-import") (part "TEST-POINT3X5"))
    )
    (comp (ref "TP3")
      (value "TEST-POINT3X5")
      (footprint "eagle-import:PAD.03X.05")
      (libsource (lib "eagle-import") (part "TEST-POINT3X5"))
    )
    (comp (ref "TP4")
      (value "TEST-POINT3X5")
      (footprint "eagle-import:PAD.03X.05")
      (libsource (lib "eagle-import") (part "TEST-POINT3X5"))
    )
    (comp (ref "TP6")
      (value "TEST-POINT3X5")
      (footprint "eagle-import:PAD.03X.05")
      (libsource (lib "eagle-import") (part "TEST-POINT3X5"))
    )
    (comp (ref "TP7")
      (value "TEST-POINT3X5")
      (footprint "eagle-import:PAD.03X.05")
      (libsource (lib "eagle-import") (part "TEST-POINT3X5"))
    )
    (comp (ref "TP8")
      (value "TEST-POINT3X5")
      (footprint "eagle-import:PAD.03X.05")
      (libsource (lib "eagle-import") (part "TEST-POINT3X5"))
    )
    (comp (ref "U$1")
      (value "NICE_NANO")
      (footprint "eagle-import:NICE_NANO")
      (libsource (lib "eagle-import") (part "NICE_NANO"))
    )
    (comp (ref "Κ_GRV")
      (value "CHERRY_MX1U")
      (footprint "eagle-import:CHERRY_MX_NO_LED_SOCKET_1U")
      (libsource (lib "eagle-import") (part "CHERRY_MX1U"))
    )
  )
  (nets
    (net (code "1") (name "/C0") (class "Default")
      (node (ref "K_1") (pin "PIN2") (pinfunction "PIN2_PIN2") (pintype "bidirectional"))
      (node (ref "K_A") (pin "PIN2") (pinfunction "PIN2_PIN2") (pintype "bidirectional"))
      (node (ref "K_CAPSLOCK") (pin "PIN2") (pinfunction "PIN2_PIN2") (pintype "bidirectional"))
      (node (ref "K_ECH") (pin "PIN2") (pinfunction "PIN2_PIN2") (pintype "bidirectional"))
      (node (ref "K_F1") (pin "PIN2") (pinfunction "PIN2_PIN2") (pintype "bidirectional"))
      (node (ref "K_LSHFT") (pin "PIN2") (pinfunction "PIN2_PIN2") (pintype "bidirectional"))
      (node (ref "K_PIPE") (pin "PIN1") (pinfunction "PIN1_PIN1") (pintype "bidirectional"))
      (node (ref "K_Q") (pin "PIN2") (pinfunction "PIN2_PIN2") (pintype "bidirectional"))
      (node (ref "K_TAB") (pin "PIN2") (pinfunction "PIN2_PIN2") (pintype "bidirectional"))
      (node (ref "U$1") (pin "P6") (pinfunction "P0.17_P6") (pintype "bidirectional"))
      (node (ref "Κ_GRV") (pin "PIN2") (pinfunction "PIN2_PIN2") (pintype "bidirectional"))
    )
    (net (code "2") (name "/C1") (class "Default")
      (node (ref "F_F2") (pin "PIN2") (pinfunction "PIN2_PIN2") (pintype "bidirectional"))
      (node (ref "K_2") (pin "PIN2") (pinfunction "PIN2_PIN2") (pintype "bidirectional"))
      (node (ref "K_3") (pin "PIN2") (pinfunction "PIN2_PIN2") (pintype "bidirectional"))
      (node (ref "K_D") (pin "PIN2") (pinfunction "PIN2_PIN2") (pintype "bidirectional"))
      (node (ref "K_E") (pin "PIN2") (pinfunction "PIN2_PIN2") (pintype "bidirectional"))
      (node (ref "K_F3") (pin "PIN2") (pinfunction "PIN2_PIN2") (pintype "bidirectional"))
      (node (ref "K_S") (pin "PIN2") (pinfunction "PIN2_PIN2") (pintype "bidirectional"))
      (node (ref "K_W") (pin "PIN2") (pinfunction "PIN2_PIN2") (pintype "bidirectional"))
      (node (ref "K_X") (pin "PIN2") (pinfunction "PIN2_PIN2") (pintype "bidirectional"))
      (node (ref "K_Z") (pin "PIN2") (pinfunction "PIN2_PIN2") (pintype "bidirectional"))
      (node (ref "U$1") (pin "P7") (pinfunction "P0.20_P7") (pintype "bidirectional"))
    )
    (net (code "3") (name "/C2") (class "Default")
      (node (ref "K_4") (pin "PIN2") (pinfunction "PIN2_PIN2") (pintype "bidirectional"))
      (node (ref "K_5") (pin "PIN2") (pinfunction "PIN2_PIN2") (pintype "bidirectional"))
      (node (ref "K_C") (pin "PIN2") (pinfunction "PIN2_PIN2") (pintype "bidirectional"))
      (node (ref "K_F") (pin "PIN2") (pinfunction "PIN2_PIN2") (pintype "bidirectional"))
      (node (ref "K_F4") (pin "PIN2") (pinfunction "PIN2_PIN2") (pintype "bidirectional"))
      (node (ref "K_F5") (pin "PIN2") (pinfunction "PIN2_PIN2") (pintype "bidirectional"))
      (node (ref "K_G") (pin "PIN2") (pinfunction "PIN2_PIN2") (pintype "bidirectional"))
      (node (ref "K_R") (pin "PIN2") (pinfunction "PIN2_PIN2") (pintype "bidirectional"))
      (node (ref "K_T") (pin "PIN2") (pinfunction "PIN2_PIN2") (pintype "bidirectional"))
      (node (ref "K_V") (pin "PIN2") (pinfunction "PIN2_PIN2") (pintype "bidirectional"))
      (node (ref "U$1") (pin "P8") (pinfunction "P0.22_P8") (pintype "bidirectional"))
    )
    (net (code "4") (name "/C3") (class "Default")
      (node (ref "K_6") (pin "PIN2") (pinfunction "PIN2_PIN2") (pintype "bidirectional"))
      (node (ref "K_7") (pin "PIN2") (pinfunction "PIN2_PIN2") (pintype "bidirectional"))
      (node (ref "K_B") (pin "PIN2") (pinfunction "PIN2_PIN2") (pintype "bidirectional"))
      (node (ref "K_F6") (pin "PIN2") (pinfunction "PIN2_PIN2") (pintype "bidirectional"))
      (node (ref "K_F7") (pin "PIN2") (pinfunction "PIN2_PIN2") (pintype "bidirectional"))
      (node (ref "K_H") (pin "PIN2") (pinfunction "PIN2_PIN2") (pintype "bidirectional"))
      (node (ref "K_J") (pin "PIN2") (pinfunction "PIN2_PIN2") (pintype "bidirectional"))
      (node (ref "K_N") (pin "PIN2") (pinfunction "PIN2_PIN2") (pintype "bidirectional"))
      (node (ref "K_U") (pin "PIN2") (pinfunction "PIN2_PIN2") (pintype "bidirectional"))
      (node (ref "K_Y") (pin "PIN2") (pinfunction "PIN2_PIN2") (pintype "bidirectional"))
      (node (ref "U$1") (pin "P9") (pinfunction "P0.24_P9") (pintype "bidirectional"))
    )
    (net (code "5") (name "/C4") (class "Default")
      (node (ref "K_8") (pin "PIN2") (pinfunction "PIN2_PIN2") (pintype "bidirectional"))
      (node (ref "K_9") (pin "PIN2") (pinfunction "PIN2_PIN2") (pintype "bidirectional"))
      (node (ref "K_COMA") (pin "PIN2") (pinfunction "PIN2_PIN2") (pintype "bidirectional"))
      (node (ref "K_F8") (pin "PIN2") (pinfunction "PIN2_PIN2") (pintype "bidirectional"))
      (node (ref "K_F9") (pin "PIN2") (pinfunction "PIN2_PIN2") (pintype "bidirectional"))
      (node (ref "K_I") (pin "PIN2") (pinfunction "PIN2_PIN2") (pintype "bidirectional"))
      (node (ref "K_K") (pin "PIN2") (pinfunction "PIN2_PIN2") (pintype "bidirectional"))
      (node (ref "K_L") (pin "PIN2") (pinfunction "PIN2_PIN2") (pintype "bidirectional"))
      (node (ref "K_M") (pin "PIN2") (pinfunction "PIN2_PIN2") (pintype "bidirectional"))
      (node (ref "K_O") (pin "PIN2") (pinfunction "PIN2_PIN2") (pintype "bidirectional"))
      (node (ref "U$1") (pin "P10") (pinfunction "P1.00_P10") (pintype "bidirectional"))
    )
    (net (code "6") (name "/C5") (class "Default")
      (node (ref "K_0") (pin "PIN2") (pinfunction "PIN2_PIN2") (pintype "bidirectional"))
      (node (ref "K_DOT") (pin "PIN2") (pinfunction "PIN2_PIN2") (pintype "bidirectional"))
      (node (ref "K_F10") (pin "PIN2") (pinfunction "PIN2_PIN2") (pintype "bidirectional"))
      (node (ref "K_F11") (pin "PIN2") (pinfunction "PIN2_PIN2") (pintype "bidirectional"))
      (node (ref "K_LBRA") (pin "PIN2") (pinfunction "PIN2_PIN2") (pintype "bidirectional"))
      (node (ref "K_MINUS") (pin "PIN2") (pinfunction "PIN2_PIN2") (pintype "bidirectional"))
      (node (ref "K_P") (pin "PIN2") (pinfunction "PIN2_PIN2") (pintype "bidirectional"))
      (node (ref "K_QUOTE") (pin "PIN2") (pinfunction "PIN2_PIN2") (pintype "bidirectional"))
      (node (ref "K_SEMIC") (pin "PIN2") (pinfunction "PIN2_PIN2") (pintype "bidirectional"))
      (node (ref "K_SLASH") (pin "PIN2") (pinfunction "PIN2_PIN2") (pintype "bidirectional"))
      (node (ref "U$1") (pin "P11") (pinfunction "P0.11_P11") (pintype "bidirectional"))
    )
    (net (code "7") (name "/C6") (class "Default")
      (node (ref "K_BACK") (pin "PIN2") (pinfunction "PIN2_PIN2") (pintype "bidirectional"))
      (node (ref "K_DELETE") (pin "PIN2") (pinfunction "PIN2_PIN2") (pintype "bidirectional"))
      (node (ref "K_ENTER") (pin "PIN2") (pinfunction "PIN2_PIN2") (pintype "bidirectional"))
      (node (ref "K_F12") (pin "PIN2") (pinfunction "PIN2_PIN2") (pintype "bidirectional"))
      (node (ref "K_PLUS") (pin "PIN2") (pinfunction "PIN2_PIN2") (pintype "bidirectional"))
      (node (ref "K_PRNT") (pin "PIN2") (pinfunction "PIN2_PIN2") (pintype "bidirectional"))
      (node (ref "K_RBRA") (pin "PIN2") (pinfunction "PIN2_PIN2") (pintype "bidirectional"))
      (node (ref "K_RSHFT") (pin "PIN2") (pinfunction "PIN2_PIN2") (pintype "bidirectional"))
      (node (ref "K_UP") (pin "PIN2") (pinfunction "PIN2_PIN2") (pintype "bidirectional"))
      (node (ref "K_WAVE") (pin "PIN2") (pinfunction "PIN2_PIN2") (pintype "bidirectional"))
      (node (ref "U$1") (pin "P12") (pinfunction "P1.04_P12") (pintype "bidirectional"))
    )
    (net (code "8") (name "/C7") (class "Default")
      (node (ref "K_END") (pin "PIN2") (pinfunction "PIN2_PIN2") (pintype "bidirectional"))
      (node (ref "K_HOME") (pin "PIN2") (pinfunction "PIN2_PIN2") (pintype "bidirectional"))
      (node (ref "K_INSERT") (pin "PIN2") (pinfunction "PIN2_PIN2") (pintype "bidirectional"))
      (node (ref "K_PAUSE") (pin "PIN2") (pinfunction "PIN2_PIN2") (pintype "bidirectional"))
      (node (ref "K_PDW") (pin "PIN2") (pinfunction "PIN2_PIN2") (pintype "bidirectional"))
      (node (ref "K_PUP") (pin "PIN2") (pinfunction "PIN2_PIN2") (pintype "bidirectional"))
      (node (ref "K_RIGHT") (pin "PIN1") (pinfunction "PIN1_PIN1") (pintype "bidirectional"))
      (node (ref "K_SCROL") (pin "PIN2") (pinfunction "PIN2_PIN2") (pintype "bidirectional"))
      (node (ref "U$1") (pin "P27") (pinfunction "P1.01_P27") (pintype "bidirectional"))
    )
    (net (code "9") (name "/C8") (class "Default")
      (node (ref "K_DOWN") (pin "PIN2") (pinfunction "PIN2_PIN2") (pintype "bidirectional"))
      (node (ref "K_FN") (pin "PIN2") (pinfunction "PIN2_PIN2") (pintype "bidirectional"))
      (node (ref "K_LALT") (pin "PIN2") (pinfunction "PIN2_PIN2") (pintype "bidirectional"))
      (node (ref "K_LCTRL") (pin "PIN2") (pinfunction "PIN2_PIN2") (pintype "bidirectional"))
      (node (ref "K_LEFT") (pin "PIN2") (pinfunction "PIN2_PIN2") (pintype "bidirectional"))
      (node (ref "K_LWIN") (pin "PIN2") (pinfunction "PIN2_PIN2") (pintype "bidirectional"))
      (node (ref "K_RALT") (pin "PIN2") (pinfunction "PIN2_PIN2") (pintype "bidirectional"))
      (node (ref "K_RCTRL") (pin "PIN2") (pinfunction "PIN2_PIN2") (pintype "bidirectional"))
      (node (ref "K_RWIN") (pin "PIN2") (pinfunction "PIN2_PIN2") (pintype "bidirectional"))
      (node (ref "K_SPACE") (pin "PIN2") (pinfunction "PIN2_PIN2") (pintype "bidirectional"))
      (node (ref "U$1") (pin "P28") (pinfunction "P1.02_P28") (pintype "bidirectional"))
    )
    (net (code "10") (name "/L0") (class "Default")
      (node (ref "D1") (pin "-") (pinfunction "-_-") (pintype "passive"))
      (node (ref "D11") (pin "-") (pinfunction "-_-") (pintype "passive"))
      (node (ref "D13") (pin "-") (pinfunction "-_-") (pintype "passive"))
      (node (ref "D15") (pin "-") (pinfunction "-_-") (pintype "passive"))
      (node (ref "D3") (pin "-") (pinfunction "-_-") (pintype "passive"))
      (node (ref "D5") (pin "-") (pinfunction "-_-") (pintype "passive"))
      (node (ref "D7") (pin "-") (pinfunction "-_-") (pintype "passive"))
      (node (ref "D86") (pin "-") (pinfunction "-_-") (pintype "passive"))
      (node (ref "D9") (pin "-") (pinfunction "-_-") (pintype "passive"))
      (node (ref "U$1") (pin "P21") (pinfunction "P0.31_P21") (pintype "bidirectional"))
    )
    (net (code "11") (name "/L1") (class "Default")
      (node (ref "D10") (pin "-") (pinfunction "-_-") (pintype "passive"))
      (node (ref "D12") (pin "-") (pinfunction "-_-") (pintype "passive"))
      (node (ref "D14") (pin "-") (pinfunction "-_-") (pintype "passive"))
      (node (ref "D16") (pin "-") (pinfunction "-_-") (pintype "passive"))
      (node (ref "D2") (pin "-") (pinfunction "-_-") (pintype "passive"))
      (node (ref "D4") (pin "-") (pinfunction "-_-") (pintype "passive"))
      (node (ref "D6") (pin "-") (pinfunction "-_-") (pintype "passive"))
      (node (ref "D8") (pin "-") (pinfunction "-_-") (pintype "passive"))
      (node (ref "D87") (pin "-") (pinfunction "-_-") (pintype "passive"))
      (node (ref "U$1") (pin "P20") (pinfunction "P0.29_P20") (pintype "bidirectional"))
    )
    (net (code "12") (name "/L2") (class "Default")
      (node (ref "D17") (pin "-") (pinfunction "-_-") (pintype "passive"))
      (node (ref "D19") (pin "-") (pinfunction "-_-") (pintype "passive"))
      (node (ref "D21") (pin "-") (pinfunction "-_-") (pintype "passive"))
      (node (ref "D23") (pin "-") (pinfunction "-_-") (pintype "passive"))
      (node (ref "D25") (pin "-") (pinfunction "-_-") (pintype "passive"))
      (node (ref "D27") (pin "-") (pinfunction "-_-") (pintype "passive"))
      (node (ref "D29") (pin "-") (pinfunction "-_-") (pintype "passive"))
      (node (ref "D31") (pin "-") (pinfunction "-_-") (pintype "passive"))
      (node (ref "D84") (pin "-") (pinfunction "-_-") (pintype "passive"))
      (node (ref "U$1") (pin "P19") (pinfunction "P0.02_P19") (pintype "bidirectional"))
    )
    (net (code "13") (name "/L3") (class "Default")
      (node (ref "D18") (pin "-") (pinfunction "-_-") (pintype "passive"))
      (node (ref "D20") (pin "-") (pinfunction "-_-") (pintype "passive"))
      (node (ref "D22") (pin "-") (pinfunction "-_-") (pintype "passive"))
      (node (ref "D24") (pin "-") (pinfunction "-_-") (pintype "passive"))
      (node (ref "D26") (pin "-") (pinfunction "-_-") (pintype "passive"))
      (node (ref "D28") (pin "-") (pinfunction "-_-") (pintype "passive"))
      (node (ref "D30") (pin "-") (pinfunction "-_-") (pintype "passive"))
      (node (ref "D32") (pin "-") (pinfunction "-_-") (pintype "passive"))
      (node (ref "D85") (pin "-") (pinfunction "-_-") (pintype "passive"))
      (node (ref "U$1") (pin "P18") (pinfunction "P1.15_P18") (pintype "bidirectional"))
    )
    (net (code "14") (name "/L4") (class "Default")
      (node (ref "D34") (pin "-") (pinfunction "-_-") (pintype "passive"))
      (node (ref "D36") (pin "-") (pinfunction "-_-") (pintype "passive"))
      (node (ref "D38") (pin "-") (pinfunction "-_-") (pintype "passive"))
      (node (ref "D40") (pin "-") (pinfunction "-_-") (pintype "passive"))
      (node (ref "D42") (pin "-") (pinfunction "-_-") (pintype "passive"))
      (node (ref "D44") (pin "-") (pinfunction "-_-") (pintype "passive"))
      (node (ref "D46") (pin "-") (pinfunction "-_-") (pintype "passive"))
      (node (ref "D49") (pin "-") (pinfunction "-_-") (pintype "passive"))
      (node (ref "D82") (pin "-") (pinfunction "-_-") (pintype "passive"))
      (node (ref "U$1") (pin "P17") (pinfunction "P1.13_P17") (pintype "bidirectional"))
    )
    (net (code "15") (name "/L5") (class "Default")
      (node (ref "D35") (pin "-") (pinfunction "-_-") (pintype "passive"))
      (node (ref "D37") (pin "-") (pinfunction "-_-") (pintype "passive"))
      (node (ref "D39") (pin "-") (pinfunction "-_-") (pintype "passive"))
      (node (ref "D41") (pin "-") (pinfunction "-_-") (pintype "passive"))
      (node (ref "D43") (pin "-") (pinfunction "-_-") (pintype "passive"))
      (node (ref "D45") (pin "-") (pinfunction "-_-") (pintype "passive"))
      (node (ref "D48") (pin "-") (pinfunction "-_-") (pintype "passive"))
      (node (ref "D50") (pin "-") (pinfunction "-_-") (pintype "passive"))
      (node (ref "D83") (pin "-") (pinfunction "-_-") (pintype "passive"))
      (node (ref "U$1") (pin "P16") (pinfunction "P1.11_P16") (pintype "bidirectional"))
    )
    (net (code "16") (name "/L6") (class "Default")
      (node (ref "D47") (pin "-") (pinfunction "-_-") (pintype "passive"))
      (node (ref "D52") (pin "-") (pinfunction "-_-") (pintype "passive"))
      (node (ref "D54") (pin "-") (pinfunction "-_-") (pintype "passive"))
      (node (ref "D56") (pin "-") (pinfunction "-_-") (pintype "passive"))
      (node (ref "D58") (pin "-") (pinfunction "-_-") (pintype "passive"))
      (node (ref "D60") (pin "-") (pinfunction "-_-") (pintype "passive"))
      (node (ref "D62") (pin "-") (pinfunction "-_-") (pintype "passive"))
      (node (ref "D81") (pin "-") (pinfunction "-_-") (pintype "passive"))
      (node (ref "D88") (pin "-") (pinfunction "-_-") (pintype "passive"))
      (node (ref "U$1") (pin "P15") (pinfunction "P0.10_P15") (pintype "bidirectional"))
    )
    (net (code "17") (name "/L7") (class "Default")
      (node (ref "D33") (pin "-") (pinfunction "-_-") (pintype "passive"))
      (node (ref "D51") (pin "-") (pinfunction "-_-") (pintype "passive"))
      (node (ref "D53") (pin "-") (pinfunction "-_-") (pintype "passive"))
      (node (ref "D55") (pin "-") (pinfunction "-_-") (pintype "passive"))
      (node (ref "D57") (pin "-") (pinfunction "-_-") (pintype "passive"))
      (node (ref "D59") (pin "-") (pinfunction "-_-") (pintype "passive"))
      (node (ref "D61") (pin "-") (pinfunction "-_-") (pintype "passive"))
      (node (ref "D63") (pin "-") (pinfunction "-_-") (pintype "passive"))
      (node (ref "D80") (pin "-") (pinfunction "-_-") (pintype "passive"))
      (node (ref "U$1") (pin "P14") (pinfunction "P0.09_P14") (pintype "bidirectional"))
    )
    (net (code "18") (name "/L8") (class "Default")
      (node (ref "D65") (pin "-") (pinfunction "-_-") (pintype "passive"))
      (node (ref "D67") (pin "-") (pinfunction "-_-") (pintype "passive"))
      (node (ref "D69") (pin "-") (pinfunction "-_-") (pintype "passive"))
      (node (ref "D71") (pin "-") (pinfunction "-_-") (pintype "passive"))
      (node (ref "D73") (pin "-") (pinfunction "-_-") (pintype "passive"))
      (node (ref "D75") (pin "-") (pinfunction "-_-") (pintype "passive"))
      (node (ref "D77") (pin "-") (pinfunction "-_-") (pintype "passive"))
      (node (ref "D79") (pin "-") (pinfunction "-_-") (pintype "passive"))
      (node (ref "U$1") (pin "P29") (pinfunction "P1.07_P29") (pintype "bidirectional"))
    )
    (net (code "19") (name "/L9") (class "Default")
      (node (ref "D64") (pin "-") (pinfunction "-_-") (pintype "passive"))
      (node (ref "D66") (pin "-") (pinfunction "-_-") (pintype "passive"))
      (node (ref "D68") (pin "-") (pinfunction "-_-") (pintype "passive"))
      (node (ref "D70") (pin "-") (pinfunction "-_-") (pintype "passive"))
      (node (ref "D72") (pin "-") (pinfunction "-_-") (pintype "passive"))
      (node (ref "D74") (pin "-") (pinfunction "-_-") (pintype "passive"))
      (node (ref "D76") (pin "-") (pinfunction "-_-") (pintype "passive"))
      (node (ref "D78") (pin "-") (pinfunction "-_-") (pintype "passive"))
      (node (ref "U$1") (pin "P13") (pinfunction "P1.06_P13") (pintype "bidirectional"))
    )
    (net (code "20") (name "/N$88") (class "Default")
      (node (ref "R_CAPS") (pin "2") (pinfunction "2_2") (pintype "passive"))
      (node (ref "U$1") (pin "P3") (pinfunction "P0.08_P3") (pintype "bidirectional"))
    )
    (net (code "21") (name "/N$89") (class "Default")
      (node (ref "R_SCROLL") (pin "2") (pinfunction "2_2") (pintype "passive"))
      (node (ref "U$1") (pin "P2") (pinfunction "P0.06_P2") (pintype "bidirectional"))
    )
    (net (code "22") (name "GND") (class "Default")
      (node (ref "D_CAPS") (pin "K") (pinfunction "C_K") (pintype "passive"))
      (node (ref "D_SCROLL") (pin "K") (pinfunction "C_K") (pintype "passive"))
      (node (ref "SW1") (pin "3") (pinfunction "3_3") (pintype "passive"))
      (node (ref "SW1") (pin "4") (pinfunction "4_4") (pintype "passive"))
      (node (ref "TP4") (pin "P$1") (pinfunction "1_P$1") (pintype "bidirectional"))
      (node (ref "TP8") (pin "P$1") (pinfunction "1_P$1") (pintype "bidirectional"))
      (node (ref "U$1") (pin "P1") (pinfunction "GND1/B-_P1") (pintype "bidirectional"))
      (node (ref "U$1") (pin "P24") (pinfunction "GND4_P24") (pintype "bidirectional"))
      (node (ref "U$1") (pin "P4") (pinfunction "GND2_P4") (pintype "bidirectional"))
      (node (ref "U$1") (pin "P5") (pinfunction "GND3_P5") (pintype "bidirectional"))
    )
    (net (code "23") (name "Net-(D1-Pad+)") (class "Default")
      (node (ref "D1") (pin "+") (pinfunction "+_+") (pintype "passive"))
      (node (ref "K_ECH") (pin "PIN1") (pinfunction "PIN1_PIN1") (pintype "bidirectional"))
    )
    (net (code "24") (name "Net-(D2-Pad+)") (class "Default")
      (node (ref "D2") (pin "+") (pinfunction "+_+") (pintype "passive"))
      (node (ref "K_F1") (pin "PIN1") (pinfunction "PIN1_PIN1") (pintype "bidirectional"))
    )
    (net (code "25") (name "Net-(D3-Pad+)") (class "Default")
      (node (ref "D3") (pin "+") (pinfunction "+_+") (pintype "passive"))
      (node (ref "F_F2") (pin "PIN1") (pinfunction "PIN1_PIN1") (pintype "bidirectional"))
    )
    (net (code "26") (name "Net-(D4-Pad+)") (class "Default")
      (node (ref "D4") (pin "+") (pinfunction "+_+") (pintype "passive"))
      (node (ref "K_F3") (pin "PIN1") (pinfunction "PIN1_PIN1") (pintype "bidirectional"))
    )
    (net (code "27") (name "Net-(D5-Pad+)") (class "Default")
      (node (ref "D5") (pin "+") (pinfunction "+_+") (pintype "passive"))
      (node (ref "K_F4") (pin "PIN1") (pinfunction "PIN1_PIN1") (pintype "bidirectional"))
    )
    (net (code "28") (name "Net-(D6-Pad+)") (class "Default")
      (node (ref "D6") (pin "+") (pinfunction "+_+") (pintype "passive"))
      (node (ref "K_F5") (pin "PIN1") (pinfunction "PIN1_PIN1") (pintype "bidirectional"))
    )
    (net (code "29") (name "Net-(D7-Pad+)") (class "Default")
      (node (ref "D7") (pin "+") (pinfunction "+_+") (pintype "passive"))
      (node (ref "K_F6") (pin "PIN1") (pinfunction "PIN1_PIN1") (pintype "bidirectional"))
    )
    (net (code "30") (name "Net-(D8-Pad+)") (class "Default")
      (node (ref "D8") (pin "+") (pinfunction "+_+") (pintype "passive"))
      (node (ref "K_F7") (pin "PIN1") (pinfunction "PIN1_PIN1") (pintype "bidirectional"))
    )
    (net (code "31") (name "Net-(D9-Pad+)") (class "Default")
      (node (ref "D9") (pin "+") (pinfunction "+_+") (pintype "passive"))
      (node (ref "K_F8") (pin "PIN1") (pinfunction "PIN1_PIN1") (pintype "bidirectional"))
    )
    (net (code "32") (name "Net-(D10-Pad+)") (class "Default")
      (node (ref "D10") (pin "+") (pinfunction "+_+") (pintype "passive"))
      (node (ref "K_F9") (pin "PIN1") (pinfunction "PIN1_PIN1") (pintype "bidirectional"))
    )
    (net (code "33") (name "Net-(D11-Pad+)") (class "Default")
      (node (ref "D11") (pin "+") (pinfunction "+_+") (pintype "passive"))
      (node (ref "K_F10") (pin "PIN1") (pinfunction "PIN1_PIN1") (pintype "bidirectional"))
    )
    (net (code "34") (name "Net-(D12-Pad+)") (class "Default")
      (node (ref "D12") (pin "+") (pinfunction "+_+") (pintype "passive"))
      (node (ref "K_F11") (pin "PIN1") (pinfunction "PIN1_PIN1") (pintype "bidirectional"))
    )
    (net (code "35") (name "Net-(D13-Pad+)") (class "Default")
      (node (ref "D13") (pin "+") (pinfunction "+_+") (pintype "passive"))
      (node (ref "K_F12") (pin "PIN1") (pinfunction "PIN1_PIN1") (pintype "bidirectional"))
    )
    (net (code "36") (name "Net-(D14-Pad+)") (class "Default")
      (node (ref "D14") (pin "+") (pinfunction "+_+") (pintype "passive"))
      (node (ref "K_PRNT") (pin "PIN1") (pinfunction "PIN1_PIN1") (pintype "bidirectional"))
    )
    (net (code "37") (name "Net-(D15-Pad+)") (class "Default")
      (node (ref "D15") (pin "+") (pinfunction "+_+") (pintype "passive"))
      (node (ref "K_SCROL") (pin "PIN1") (pinfunction "PIN1_PIN1") (pintype "bidirectional"))
    )
    (net (code "38") (name "Net-(D16-Pad+)") (class "Default")
      (node (ref "D16") (pin "+") (pinfunction "+_+") (pintype "passive"))
      (node (ref "K_PAUSE") (pin "PIN1") (pinfunction "PIN1_PIN1") (pintype "bidirectional"))
    )
    (net (code "39") (name "Net-(D17-Pad+)") (class "Default")
      (node (ref "D17") (pin "+") (pinfunction "+_+") (pintype "passive"))
      (node (ref "Κ_GRV") (pin "PIN1") (pinfunction "PIN1_PIN1") (pintype "bidirectional"))
    )
    (net (code "40") (name "Net-(D18-Pad+)") (class "Default")
      (node (ref "D18") (pin "+") (pinfunction "+_+") (pintype "passive"))
      (node (ref "K_1") (pin "PIN1") (pinfunction "PIN1_PIN1") (pintype "bidirectional"))
    )
    (net (code "41") (name "Net-(D19-Pad+)") (class "Default")
      (node (ref "D19") (pin "+") (pinfunction "+_+") (pintype "passive"))
      (node (ref "K_2") (pin "PIN1") (pinfunction "PIN1_PIN1") (pintype "bidirectional"))
    )
    (net (code "42") (name "Net-(D20-Pad+)") (class "Default")
      (node (ref "D20") (pin "+") (pinfunction "+_+") (pintype "passive"))
      (node (ref "K_3") (pin "PIN1") (pinfunction "PIN1_PIN1") (pintype "bidirectional"))
    )
    (net (code "43") (name "Net-(D21-Pad+)") (class "Default")
      (node (ref "D21") (pin "+") (pinfunction "+_+") (pintype "passive"))
      (node (ref "K_4") (pin "PIN1") (pinfunction "PIN1_PIN1") (pintype "bidirectional"))
    )
    (net (code "44") (name "Net-(D22-Pad+)") (class "Default")
      (node (ref "D22") (pin "+") (pinfunction "+_+") (pintype "passive"))
      (node (ref "K_5") (pin "PIN1") (pinfunction "PIN1_PIN1") (pintype "bidirectional"))
    )
    (net (code "45") (name "Net-(D23-Pad+)") (class "Default")
      (node (ref "D23") (pin "+") (pinfunction "+_+") (pintype "passive"))
      (node (ref "K_6") (pin "PIN1") (pinfunction "PIN1_PIN1") (pintype "bidirectional"))
    )
    (net (code "46") (name "Net-(D24-Pad+)") (class "Default")
      (node (ref "D24") (pin "+") (pinfunction "+_+") (pintype "passive"))
      (node (ref "K_7") (pin "PIN1") (pinfunction "PIN1_PIN1") (pintype "bidirectional"))
    )
    (net (code "47") (name "Net-(D25-Pad+)") (class "Default")
      (node (ref "D25") (pin "+") (pinfunction "+_+") (pintype "passive"))
      (node (ref "K_8") (pin "PIN1") (pinfunction "PIN1_PIN1") (pintype "bidirectional"))
    )
    (net (code "48") (name "Net-(D26-Pad+)") (class "Default")
      (node (ref "D26") (pin "+") (pinfunction "+_+") (pintype "passive"))
      (node (ref "K_9") (pin "PIN1") (pinfunction "PIN1_PIN1") (pintype "bidirectional"))
    )
    (net (code "49") (name "Net-(D27-Pad+)") (class "Default")
      (node (ref "D27") (pin "+") (pinfunction "+_+") (pintype "passive"))
      (node (ref "K_0") (pin "PIN1") (pinfunction "PIN1_PIN1") (pintype "bidirectional"))
    )
    (net (code "50") (name "Net-(D28-Pad+)") (class "Default")
      (node (ref "D28") (pin "+") (pinfunction "+_+") (pintype "passive"))
      (node (ref "K_MINUS") (pin "PIN1") (pinfunction "PIN1_PIN1") (pintype "bidirectional"))
    )
    (net (code "51") (name "Net-(D29-Pad+)") (class "Default")
      (node (ref "D29") (pin "+") (pinfunction "+_+") (pintype "passive"))
      (node (ref "K_PLUS") (pin "PIN1") (pinfunction "PIN1_PIN1") (pintype "bidirectional"))
    )
    (net (code "52") (name "Net-(D30-Pad+)") (class "Default")
      (node (ref "D30") (pin "+") (pinfunction "+_+") (pintype "passive"))
      (node (ref "K_BACK") (pin "PIN1") (pinfunction "PIN1_PIN1") (pintype "bidirectional"))
    )
    (net (code "53") (name "Net-(D31-Pad+)") (class "Default")
      (node (ref "D31") (pin "+") (pinfunction "+_+") (pintype "passive"))
      (node (ref "K_INSERT") (pin "PIN1") (pinfunction "PIN1_PIN1") (pintype "bidirectional"))
    )
    (net (code "54") (name "Net-(D32-Pad+)") (class "Default")
      (node (ref "D32") (pin "+") (pinfunction "+_+") (pintype "passive"))
      (node (ref "K_HOME") (pin "PIN1") (pinfunction "PIN1_PIN1") (pintype "bidirectional"))
    )
    (net (code "55") (name "Net-(D33-Pad+)") (class "Default")
      (node (ref "D33") (pin "+") (pinfunction "+_+") (pintype "passive"))
      (node (ref "K_PUP") (pin "PIN1") (pinfunction "PIN1_PIN1") (pintype "bidirectional"))
    )
    (net (code "56") (name "Net-(D34-Pad+)") (class "Default")
      (node (ref "D34") (pin "+") (pinfunction "+_+") (pintype "passive"))
      (node (ref "K_TAB") (pin "PIN1") (pinfunction "PIN1_PIN1") (pintype "bidirectional"))
    )
    (net (code "57") (name "Net-(D35-Pad+)") (class "Default")
      (node (ref "D35") (pin "+") (pinfunction "+_+") (pintype "passive"))
      (node (ref "K_Q") (pin "PIN1") (pinfunction "PIN1_PIN1") (pintype "bidirectional"))
    )
    (net (code "58") (name "Net-(D36-Pad+)") (class "Default")
      (node (ref "D36") (pin "+") (pinfunction "+_+") (pintype "passive"))
      (node (ref "K_W") (pin "PIN1") (pinfunction "PIN1_PIN1") (pintype "bidirectional"))
    )
    (net (code "59") (name "Net-(D37-Pad+)") (class "Default")
      (node (ref "D37") (pin "+") (pinfunction "+_+") (pintype "passive"))
      (node (ref "K_E") (pin "PIN1") (pinfunction "PIN1_PIN1") (pintype "bidirectional"))
    )
    (net (code "60") (name "Net-(D38-Pad+)") (class "Default")
      (node (ref "D38") (pin "+") (pinfunction "+_+") (pintype "passive"))
      (node (ref "K_R") (pin "PIN1") (pinfunction "PIN1_PIN1") (pintype "bidirectional"))
    )
    (net (code "61") (name "Net-(D39-Pad+)") (class "Default")
      (node (ref "D39") (pin "+") (pinfunction "+_+") (pintype "passive"))
      (node (ref "K_T") (pin "PIN1") (pinfunction "PIN1_PIN1") (pintype "bidirectional"))
    )
    (net (code "62") (name "Net-(D40-Pad+)") (class "Default")
      (node (ref "D40") (pin "+") (pinfunction "+_+") (pintype "passive"))
      (node (ref "K_Y") (pin "PIN1") (pinfunction "PIN1_PIN1") (pintype "bidirectional"))
    )
    (net (code "63") (name "Net-(D41-Pad+)") (class "Default")
      (node (ref "D41") (pin "+") (pinfunction "+_+") (pintype "passive"))
      (node (ref "K_U") (pin "PIN1") (pinfunction "PIN1_PIN1") (pintype "bidirectional"))
    )
    (net (code "64") (name "Net-(D42-Pad+)") (class "Default")
      (node (ref "D42") (pin "+") (pinfunction "+_+") (pintype "passive"))
      (node (ref "K_I") (pin "PIN1") (pinfunction "PIN1_PIN1") (pintype "bidirectional"))
    )
    (net (code "65") (name "Net-(D43-Pad+)") (class "Default")
      (node (ref "D43") (pin "+") (pinfunction "+_+") (pintype "passive"))
      (node (ref "K_O") (pin "PIN1") (pinfunction "PIN1_PIN1") (pintype "bidirectional"))
    )
    (net (code "66") (name "Net-(D44-Pad+)") (class "Default")
      (node (ref "D44") (pin "+") (pinfunction "+_+") (pintype "passive"))
      (node (ref "K_P") (pin "PIN1") (pinfunction "PIN1_PIN1") (pintype "bidirectional"))
    )
    (net (code "67") (name "Net-(D45-Pad+)") (class "Default")
      (node (ref "D45") (pin "+") (pinfunction "+_+") (pintype "passive"))
      (node (ref "K_LBRA") (pin "PIN1") (pinfunction "PIN1_PIN1") (pintype "bidirectional"))
    )
    (net (code "68") (name "Net-(D46-Pad+)") (class "Default")
      (node (ref "D46") (pin "+") (pinfunction "+_+") (pintype "passive"))
      (node (ref "K_RBRA") (pin "PIN1") (pinfunction "PIN1_PIN1") (pintype "bidirectional"))
    )
    (net (code "69") (name "Net-(D47-Pad+)") (class "Default")
      (node (ref "D47") (pin "+") (pinfunction "+_+") (pintype "passive"))
      (node (ref "K_ENTER") (pin "PIN1") (pinfunction "PIN1_PIN1") (pintype "bidirectional"))
    )
    (net (code "70") (name "Net-(D48-Pad+)") (class "Default")
      (node (ref "D48") (pin "+") (pinfunction "+_+") (pintype "passive"))
      (node (ref "K_DELETE") (pin "PIN1") (pinfunction "PIN1_PIN1") (pintype "bidirectional"))
    )
    (net (code "71") (name "Net-(D49-Pad+)") (class "Default")
      (node (ref "D49") (pin "+") (pinfunction "+_+") (pintype "passive"))
      (node (ref "K_END") (pin "PIN1") (pinfunction "PIN1_PIN1") (pintype "bidirectional"))
    )
    (net (code "72") (name "Net-(D50-Pad+)") (class "Default")
      (node (ref "D50") (pin "+") (pinfunction "+_+") (pintype "passive"))
      (node (ref "K_PDW") (pin "PIN1") (pinfunction "PIN1_PIN1") (pintype "bidirectional"))
    )
    (net (code "73") (name "Net-(D51-Pad+)") (class "Default")
      (node (ref "D51") (pin "+") (pinfunction "+_+") (pintype "passive"))
      (node (ref "K_CAPSLOCK") (pin "PIN1") (pinfunction "PIN1_PIN1") (pintype "bidirectional"))
    )
    (net (code "74") (name "Net-(D52-Pad+)") (class "Default")
      (node (ref "D52") (pin "+") (pinfunction "+_+") (pintype "passive"))
      (node (ref "K_A") (pin "PIN1") (pinfunction "PIN1_PIN1") (pintype "bidirectional"))
    )
    (net (code "75") (name "Net-(D53-Pad+)") (class "Default")
      (node (ref "D53") (pin "+") (pinfunction "+_+") (pintype "passive"))
      (node (ref "K_S") (pin "PIN1") (pinfunction "PIN1_PIN1") (pintype "bidirectional"))
    )
    (net (code "76") (name "Net-(D54-Pad+)") (class "Default")
      (node (ref "D54") (pin "+") (pinfunction "+_+") (pintype "passive"))
      (node (ref "K_D") (pin "PIN1") (pinfunction "PIN1_PIN1") (pintype "bidirectional"))
    )
    (net (code "77") (name "Net-(D55-Pad+)") (class "Default")
      (node (ref "D55") (pin "+") (pinfunction "+_+") (pintype "passive"))
      (node (ref "K_F") (pin "PIN1") (pinfunction "PIN1_PIN1") (pintype "bidirectional"))
    )
    (net (code "78") (name "Net-(D56-Pad+)") (class "Default")
      (node (ref "D56") (pin "+") (pinfunction "+_+") (pintype "passive"))
      (node (ref "K_G") (pin "PIN1") (pinfunction "PIN1_PIN1") (pintype "bidirectional"))
    )
    (net (code "79") (name "Net-(D57-Pad+)") (class "Default")
      (node (ref "D57") (pin "+") (pinfunction "+_+") (pintype "passive"))
      (node (ref "K_H") (pin "PIN1") (pinfunction "PIN1_PIN1") (pintype "bidirectional"))
    )
    (net (code "80") (name "Net-(D58-Pad+)") (class "Default")
      (node (ref "D58") (pin "+") (pinfunction "+_+") (pintype "passive"))
      (node (ref "K_J") (pin "PIN1") (pinfunction "PIN1_PIN1") (pintype "bidirectional"))
    )
    (net (code "81") (name "Net-(D59-Pad+)") (class "Default")
      (node (ref "D59") (pin "+") (pinfunction "+_+") (pintype "passive"))
      (node (ref "K_K") (pin "PIN1") (pinfunction "PIN1_PIN1") (pintype "bidirectional"))
    )
    (net (code "82") (name "Net-(D60-Pad+)") (class "Default")
      (node (ref "D60") (pin "+") (pinfunction "+_+") (pintype "passive"))
      (node (ref "K_L") (pin "PIN1") (pinfunction "PIN1_PIN1") (pintype "bidirectional"))
    )
    (net (code "83") (name "Net-(D61-Pad+)") (class "Default")
      (node (ref "D61") (pin "+") (pinfunction "+_+") (pintype "passive"))
      (node (ref "K_SEMIC") (pin "PIN1") (pinfunction "PIN1_PIN1") (pintype "bidirectional"))
    )
    (net (code "84") (name "Net-(D62-Pad+)") (class "Default")
      (node (ref "D62") (pin "+") (pinfunction "+_+") (pintype "passive"))
      (node (ref "K_QUOTE") (pin "PIN1") (pinfunction "PIN1_PIN1") (pintype "bidirectional"))
    )
    (net (code "85") (name "Net-(D63-Pad+)") (class "Default")
      (node (ref "D63") (pin "+") (pinfunction "+_+") (pintype "passive"))
      (node (ref "K_WAVE") (pin "PIN1") (pinfunction "PIN1_PIN1") (pintype "bidirectional"))
    )
    (net (code "86") (name "Net-(D64-Pad+)") (class "Default")
      (node (ref "D64") (pin "+") (pinfunction "+_+") (pintype "passive"))
      (node (ref "K_LSHFT") (pin "PIN1") (pinfunction "PIN1_PIN1") (pintype "bidirectional"))
    )
    (net (code "87") (name "Net-(D65-Pad+)") (class "Default")
      (node (ref "D65") (pin "+") (pinfunction "+_+") (pintype "passive"))
      (node (ref "K_PIPE") (pin "PIN2") (pinfunction "PIN2_PIN2") (pintype "bidirectional"))
    )
    (net (code "88") (name "Net-(D66-Pad+)") (class "Default")
      (node (ref "D66") (pin "+") (pinfunction "+_+") (pintype "passive"))
      (node (ref "K_Z") (pin "PIN1") (pinfunction "PIN1_PIN1") (pintype "bidirectional"))
    )
    (net (code "89") (name "Net-(D67-Pad+)") (class "Default")
      (node (ref "D67") (pin "+") (pinfunction "+_+") (pintype "passive"))
      (node (ref "K_X") (pin "PIN1") (pinfunction "PIN1_PIN1") (pintype "bidirectional"))
    )
    (net (code "90") (name "Net-(D68-Pad+)") (class "Default")
      (node (ref "D68") (pin "+") (pinfunction "+_+") (pintype "passive"))
      (node (ref "K_C") (pin "PIN1") (pinfunction "PIN1_PIN1") (pintype "bidirectional"))
    )
    (net (code "91") (name "Net-(D69-Pad+)") (class "Default")
      (node (ref "D69") (pin "+") (pinfunction "+_+") (pintype "passive"))
      (node (ref "K_V") (pin "PIN1") (pinfunction "PIN1_PIN1") (pintype "bidirectional"))
    )
    (net (code "92") (name "Net-(D70-Pad+)") (class "Default")
      (node (ref "D70") (pin "+") (pinfunction "+_+") (pintype "passive"))
      (node (ref "K_B") (pin "PIN1") (pinfunction "PIN1_PIN1") (pintype "bidirectional"))
    )
    (net (code "93") (name "Net-(D71-Pad+)") (class "Default")
      (node (ref "D71") (pin "+") (pinfunction "+_+") (pintype "passive"))
      (node (ref "K_N") (pin "PIN1") (pinfunction "PIN1_PIN1") (pintype "bidirectional"))
    )
    (net (code "94") (name "Net-(D72-Pad+)") (class "Default")
      (node (ref "D72") (pin "+") (pinfunction "+_+") (pintype "passive"))
      (node (ref "K_M") (pin "PIN1") (pinfunction "PIN1_PIN1") (pintype "bidirectional"))
    )
    (net (code "95") (name "Net-(D73-Pad+)") (class "Default")
      (node (ref "D73") (pin "+") (pinfunction "+_+") (pintype "passive"))
      (node (ref "K_COMA") (pin "PIN1") (pinfunction "PIN1_PIN1") (pintype "bidirectional"))
    )
    (net (code "96") (name "Net-(D74-Pad+)") (class "Default")
      (node (ref "D74") (pin "+") (pinfunction "+_+") (pintype "passive"))
      (node (ref "K_DOT") (pin "PIN1") (pinfunction "PIN1_PIN1") (pintype "bidirectional"))
    )
    (net (code "97") (name "Net-(D75-Pad+)") (class "Default")
      (node (ref "D75") (pin "+") (pinfunction "+_+") (pintype "passive"))
      (node (ref "K_SLASH") (pin "PIN1") (pinfunction "PIN1_PIN1") (pintype "bidirectional"))
    )
    (net (code "98") (name "Net-(D76-Pad+)") (class "Default")
      (node (ref "D76") (pin "+") (pinfunction "+_+") (pintype "passive"))
      (node (ref "K_RSHFT") (pin "PIN1") (pinfunction "PIN1_PIN1") (pintype "bidirectional"))
    )
    (net (code "99") (name "Net-(D77-Pad+)") (class "Default")
      (node (ref "D77") (pin "+") (pinfunction "+_+") (pintype "passive"))
      (node (ref "K_UP") (pin "PIN1") (pinfunction "PIN1_PIN1") (pintype "bidirectional"))
    )
    (net (code "100") (name "Net-(D78-Pad+)") (class "Default")
      (node (ref "D78") (pin "+") (pinfunction "+_+") (pintype "passive"))
      (node (ref "K_LCTRL") (pin "PIN1") (pinfunction "PIN1_PIN1") (pintype "bidirectional"))
    )
    (net (code "101") (name "Net-(D79-Pad+)") (class "Default")
      (node (ref "D79") (pin "+") (pinfunction "+_+") (pintype "passive"))
      (node (ref "K_LWIN") (pin "PIN1") (pinfunction "PIN1_PIN1") (pintype "bidirectional"))
    )
    (net (code "102") (name "Net-(D80-Pad+)") (class "Default")
      (node (ref "D80") (pin "+") (pinfunction "+_+") (pintype "passive"))
      (node (ref "K_LALT") (pin "PIN1") (pinfunction "PIN1_PIN1") (pintype "bidirectional"))
    )
    (net (code "103") (name "Net-(D81-Pad+)") (class "Default")
      (node (ref "D81") (pin "+") (pinfunction "+_+") (pintype "passive"))
      (node (ref "K_SPACE") (pin "PIN1") (pinfunction "PIN1_PIN1") (pintype "bidirectional"))
    )
    (net (code "104") (name "Net-(D82-Pad+)") (class "Default")
      (node (ref "D82") (pin "+") (pinfunction "+_+") (pintype "passive"))
      (node (ref "K_RALT") (pin "PIN1") (pinfunction "PIN1_PIN1") (pintype "bidirectional"))
    )
    (net (code "105") (name "Net-(D83-Pad+)") (class "Default")
      (node (ref "D83") (pin "+") (pinfunction "+_+") (pintype "passive"))
      (node (ref "K_RWIN") (pin "PIN1") (pinfunction "PIN1_PIN1") (pintype "bidirectional"))
    )
    (net (code "106") (name "Net-(D84-Pad+)") (class "Default")
      (node (ref "D84") (pin "+") (pinfunction "+_+") (pintype "passive"))
      (node (ref "K_RCTRL") (pin "PIN1") (pinfunction "PIN1_PIN1") (pintype "bidirectional"))
    )
    (net (code "107") (name "Net-(D85-Pad+)") (class "Default")
      (node (ref "D85") (pin "+") (pinfunction "+_+") (pintype "passive"))
      (node (ref "K_FN") (pin "PIN1") (pinfunction "PIN1_PIN1") (pintype "bidirectional"))
    )
    (net (code "108") (name "Net-(D86-Pad+)") (class "Default")
      (node (ref "D86") (pin "+") (pinfunction "+_+") (pintype "passive"))
      (node (ref "K_LEFT") (pin "PIN1") (pinfunction "PIN1_PIN1") (pintype "bidirectional"))
    )
    (net (code "109") (name "Net-(D87-Pad+)") (class "Default")
      (node (ref "D87") (pin "+") (pinfunction "+_+") (pintype "passive"))
      (node (ref "K_DOWN") (pin "PIN1") (pinfunction "PIN1_PIN1") (pintype "bidirectional"))
    )
    (net (code "110") (name "Net-(D88-Pad+)") (class "Default")
      (node (ref "D88") (pin "+") (pinfunction "+_+") (pintype "passive"))
      (node (ref "K_RIGHT") (pin "PIN2") (pinfunction "PIN2_PIN2") (pintype "bidirectional"))
    )
    (net (code "111") (name "Net-(D_CAPS-PadA)") (class "Default")
      (node (ref "D_CAPS") (pin "A") (pinfunction "A_A") (pintype "passive"))
      (node (ref "R_CAPS") (pin "1") (pinfunction "1_1") (pintype "passive"))
    )
    (net (code "112") (name "Net-(D_SCROLL-PadA)") (class "Default")
      (node (ref "D_SCROLL") (pin "A") (pinfunction "A_A") (pintype "passive"))
      (node (ref "R_SCROLL") (pin "1") (pinfunction "1_1") (pintype "passive"))
    )
    (net (code "113") (name "Net-(TP1-1)") (class "Default")
      (node (ref "TP1") (pin "P$1") (pinfunction "1_P$1") (pintype "bidirectional"))
      (node (ref "TP6") (pin "P$1") (pinfunction "1_P$1") (pintype "bidirectional"))
      (node (ref "U$1") (pin "P26") (pinfunction "B+_P26") (pintype "bidirectional"))
    )
    (net (code "114") (name "Net-(TP3-1)") (class "Default")
      (node (ref "TP3") (pin "P$1") (pinfunction "1_P$1") (pintype "bidirectional"))
      (node (ref "TP7") (pin "P$1") (pinfunction "1_P$1") (pintype "bidirectional"))
      (node (ref "U$1") (pin "P25") (pinfunction "RAW/B+_P25") (pintype "bidirectional"))
    )
    (net (code "115") (name "Net-(U$1-VCC3V3)") (class "Default")
      (node (ref "R_RESETPU") (pin "1") (pinfunction "1_1") (pintype "passive"))
      (node (ref "U$1") (pin "P22") (pinfunction "VCC3V3_P22") (pintype "bidirectional"))
    )
    (net (code "116") (name "Net-(U$1-~{RESET})") (class "Default")
      (node (ref "R_RESETPU") (pin "2") (pinfunction "2_2") (pintype "passive"))
      (node (ref "SW1") (pin "1") (pinfunction "1_1") (pintype "passive"))
      (node (ref "SW1") (pin "2") (pinfunction "2_2") (pintype "passive"))
      (node (ref "U$1") (pin "P23") (pinfunction "~{RESET}_P23") (pintype "bidirectional"))
    )
  )
)
